# schmatic.net
KiCad netlist of a schematic drawn in EAGLE
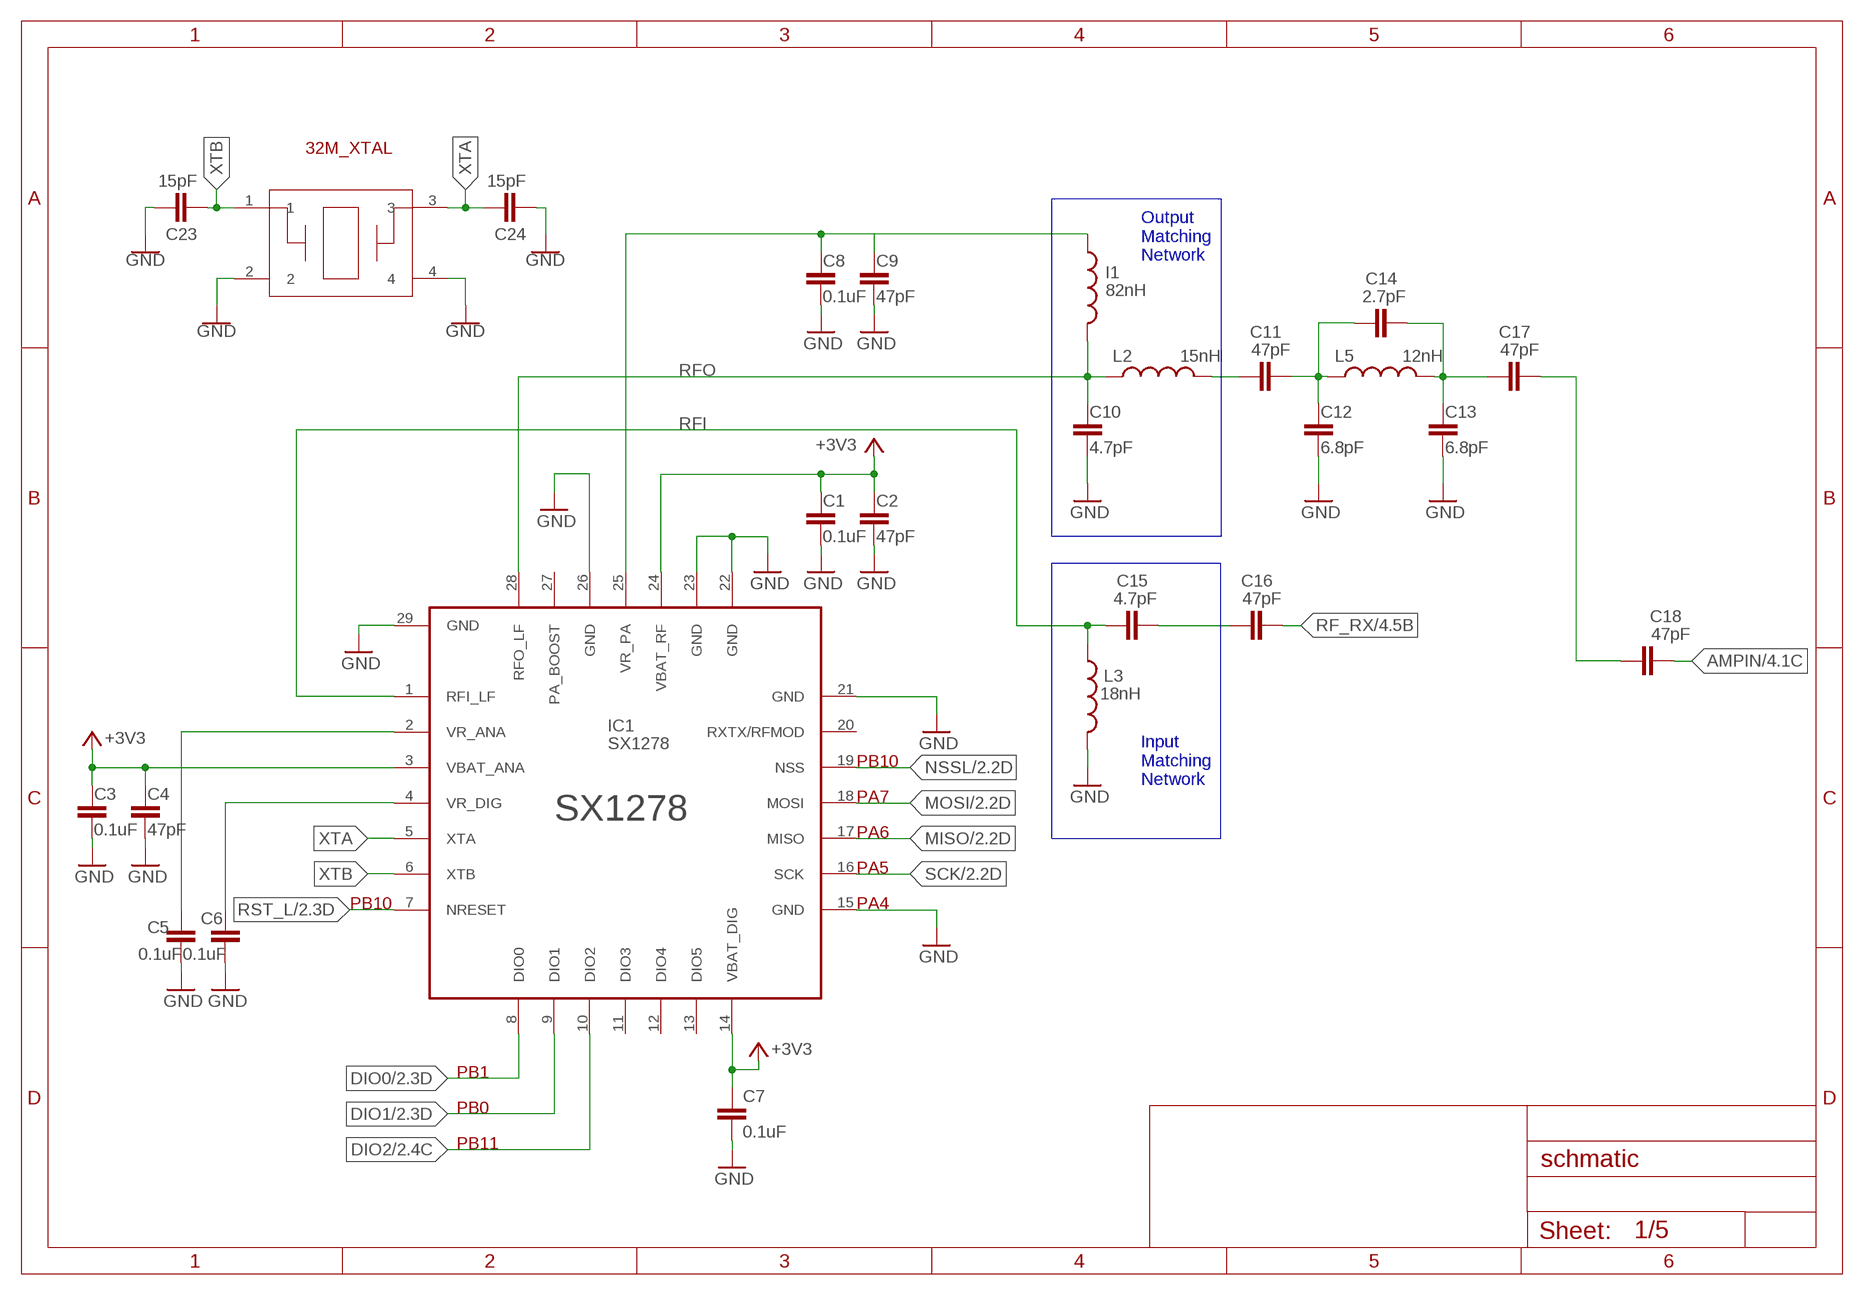
[diagram p0: schematic, sheet 1]
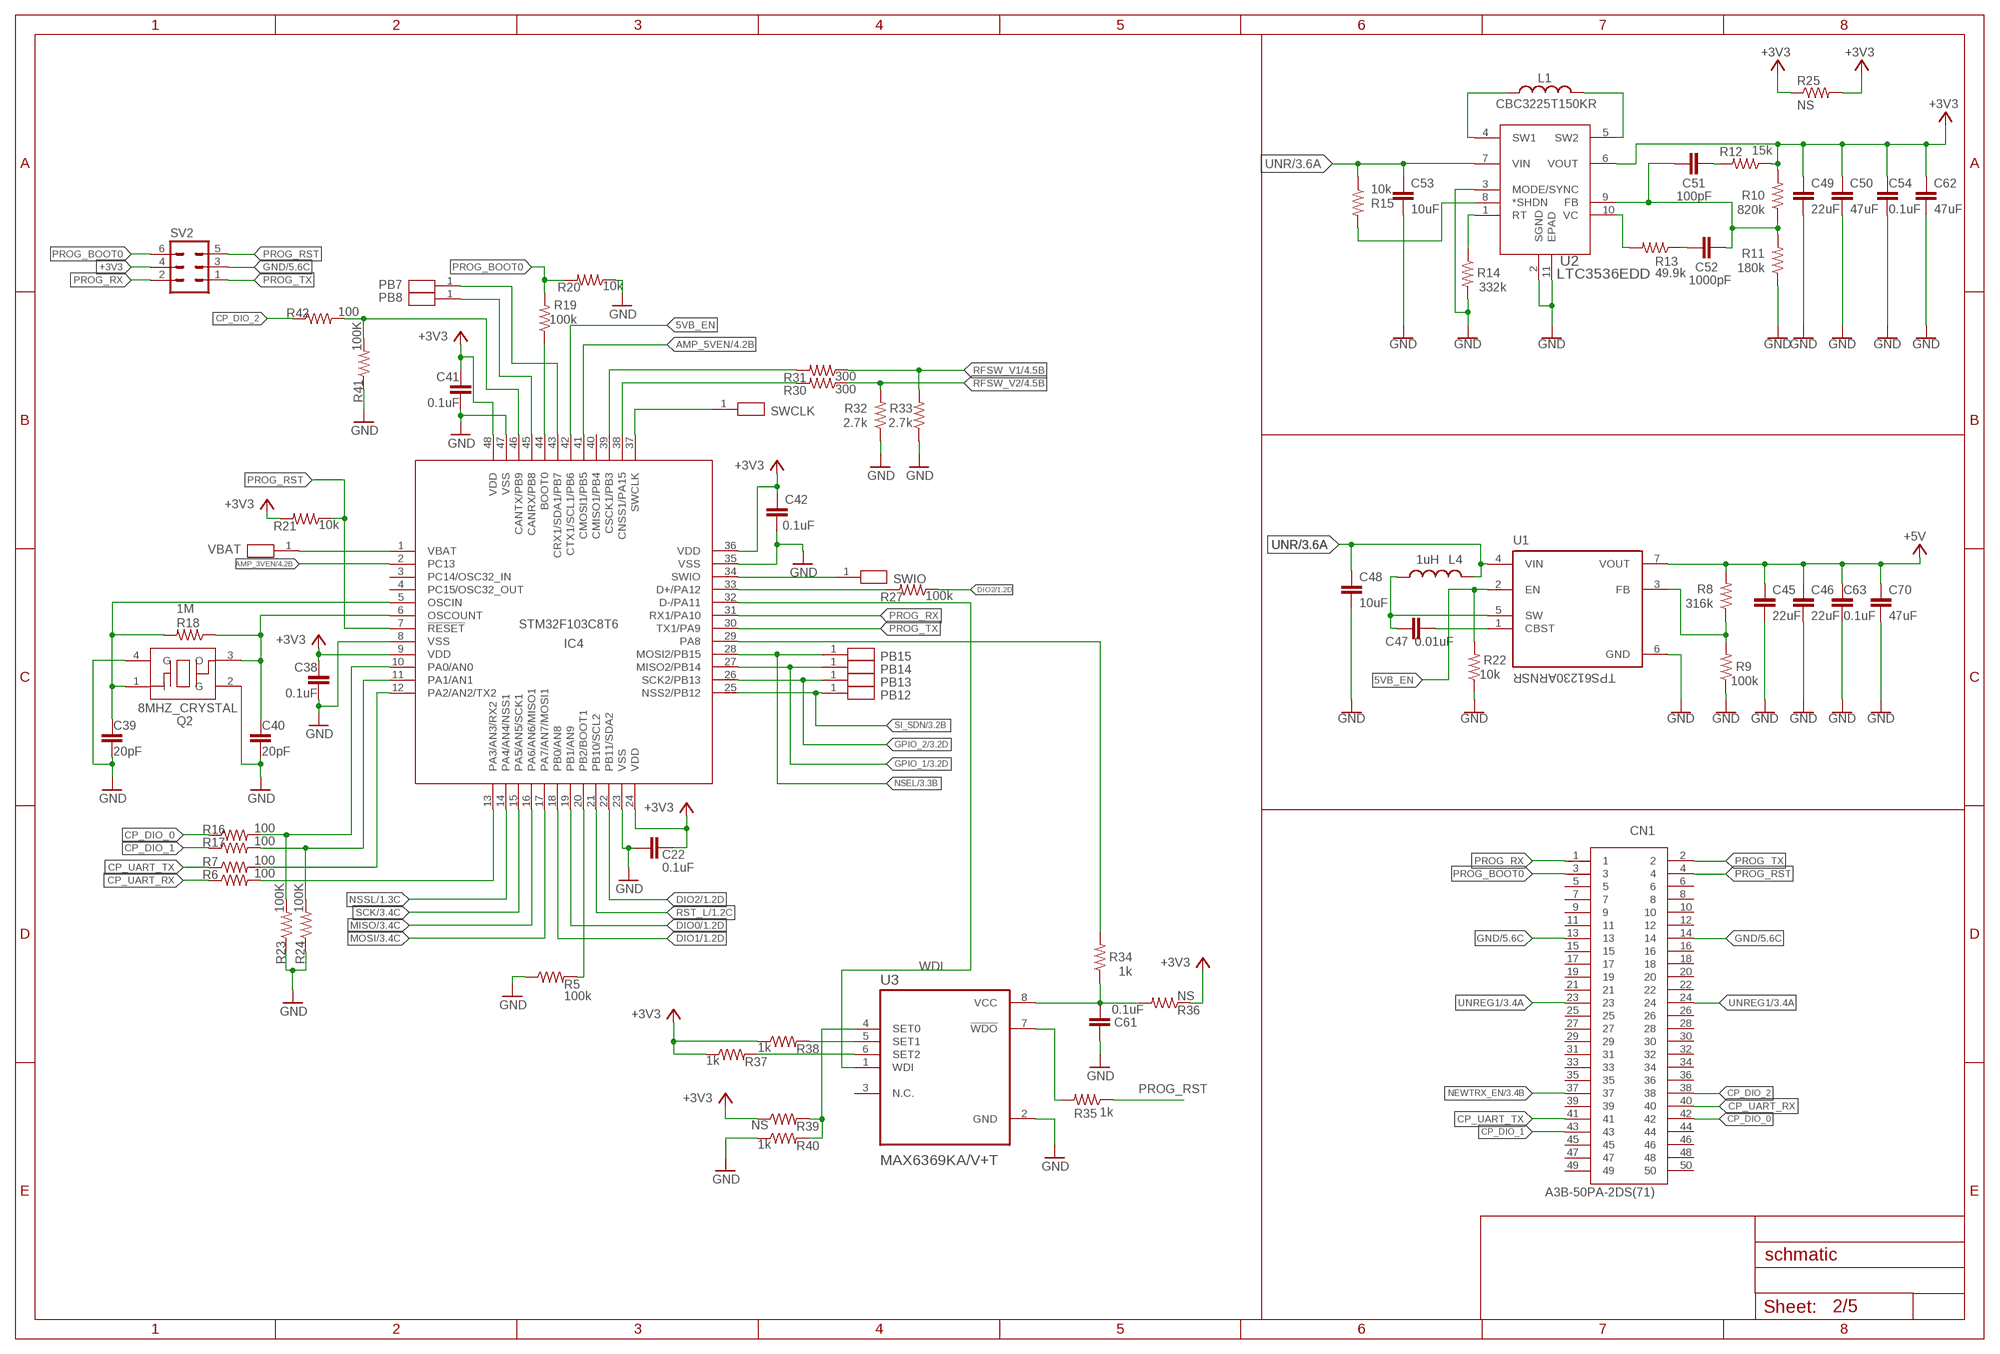
[diagram p1: schematic, sheet 2]
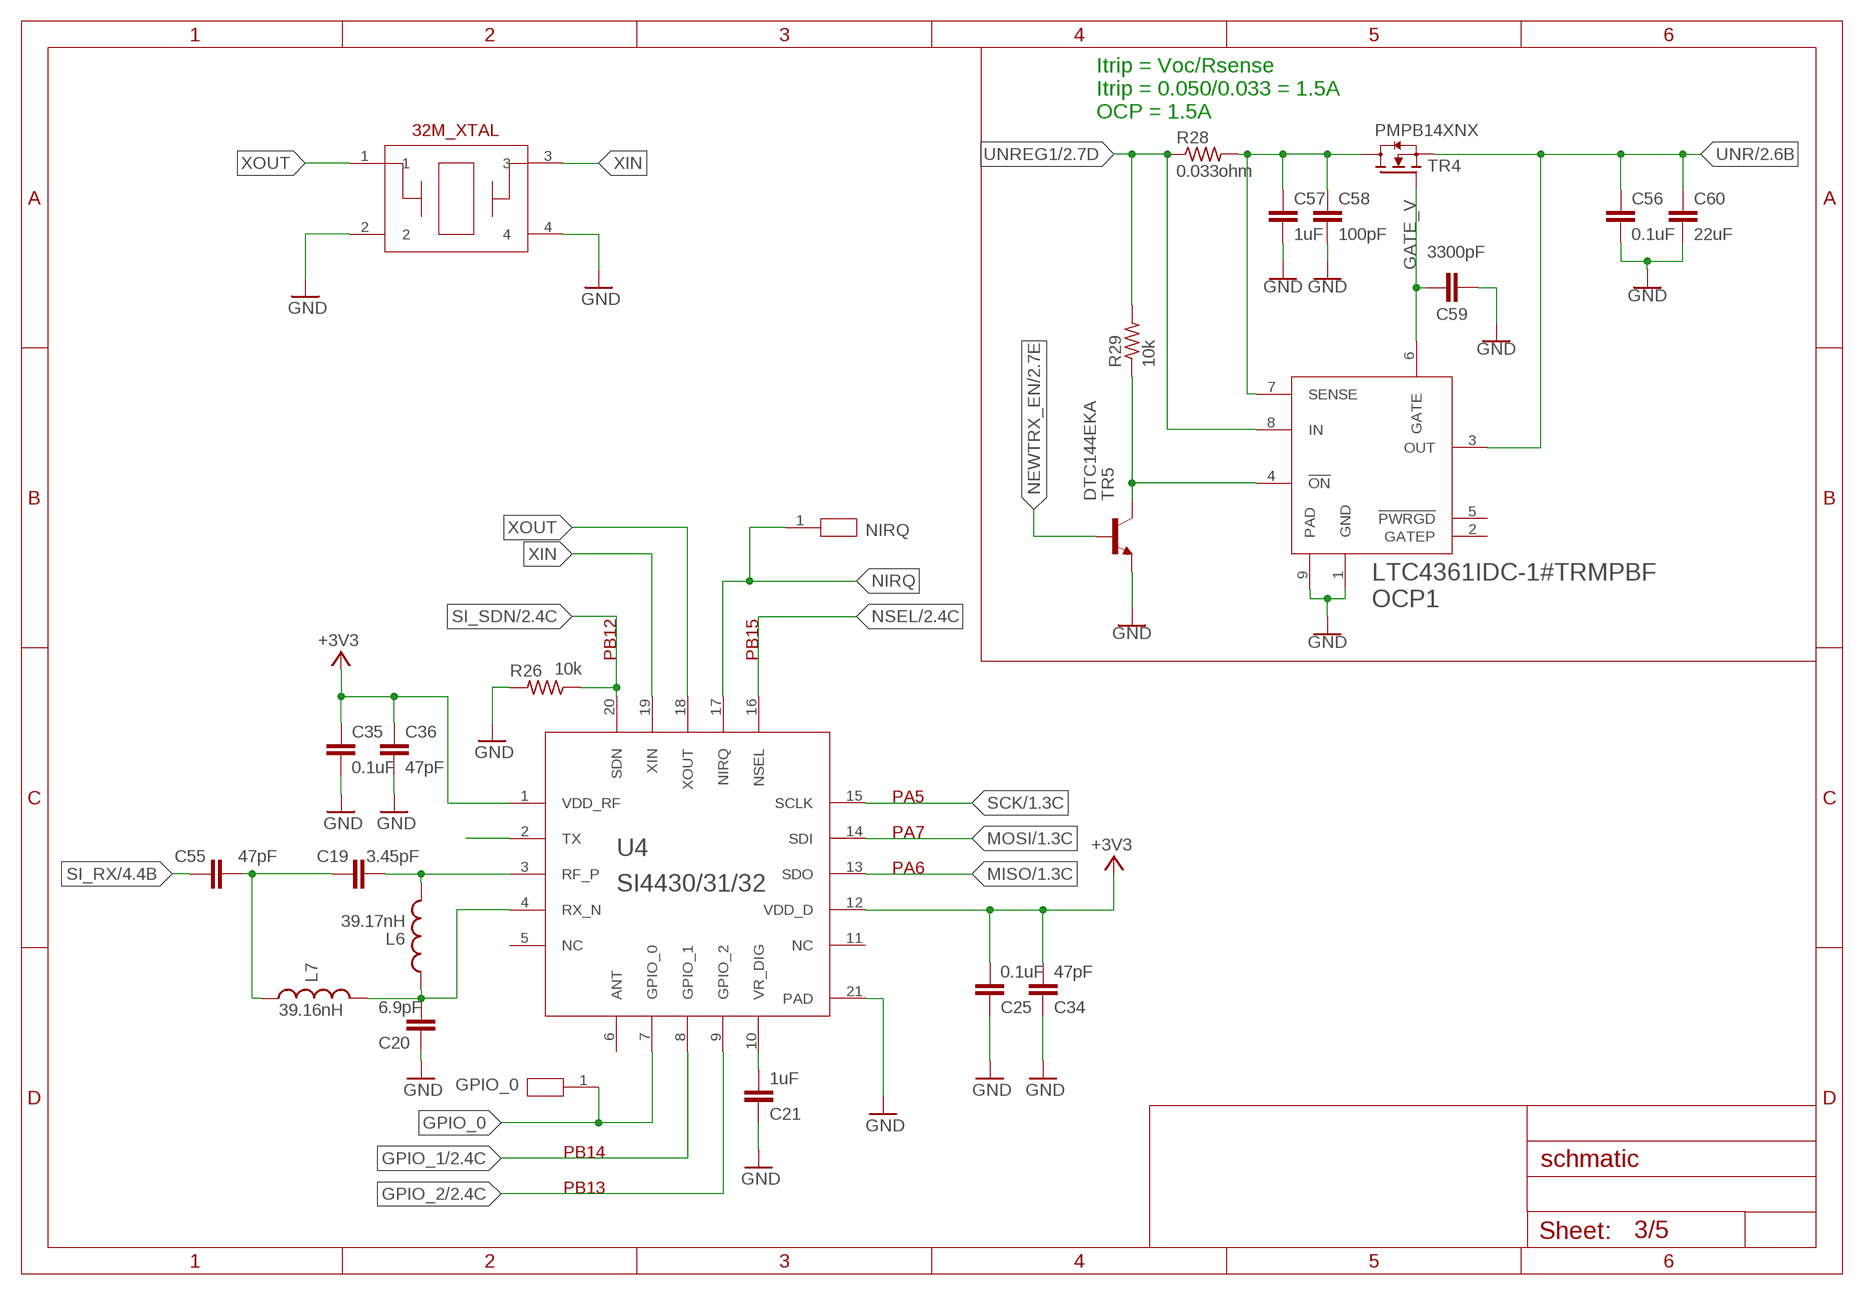
[diagram p2: schematic, sheet 3]
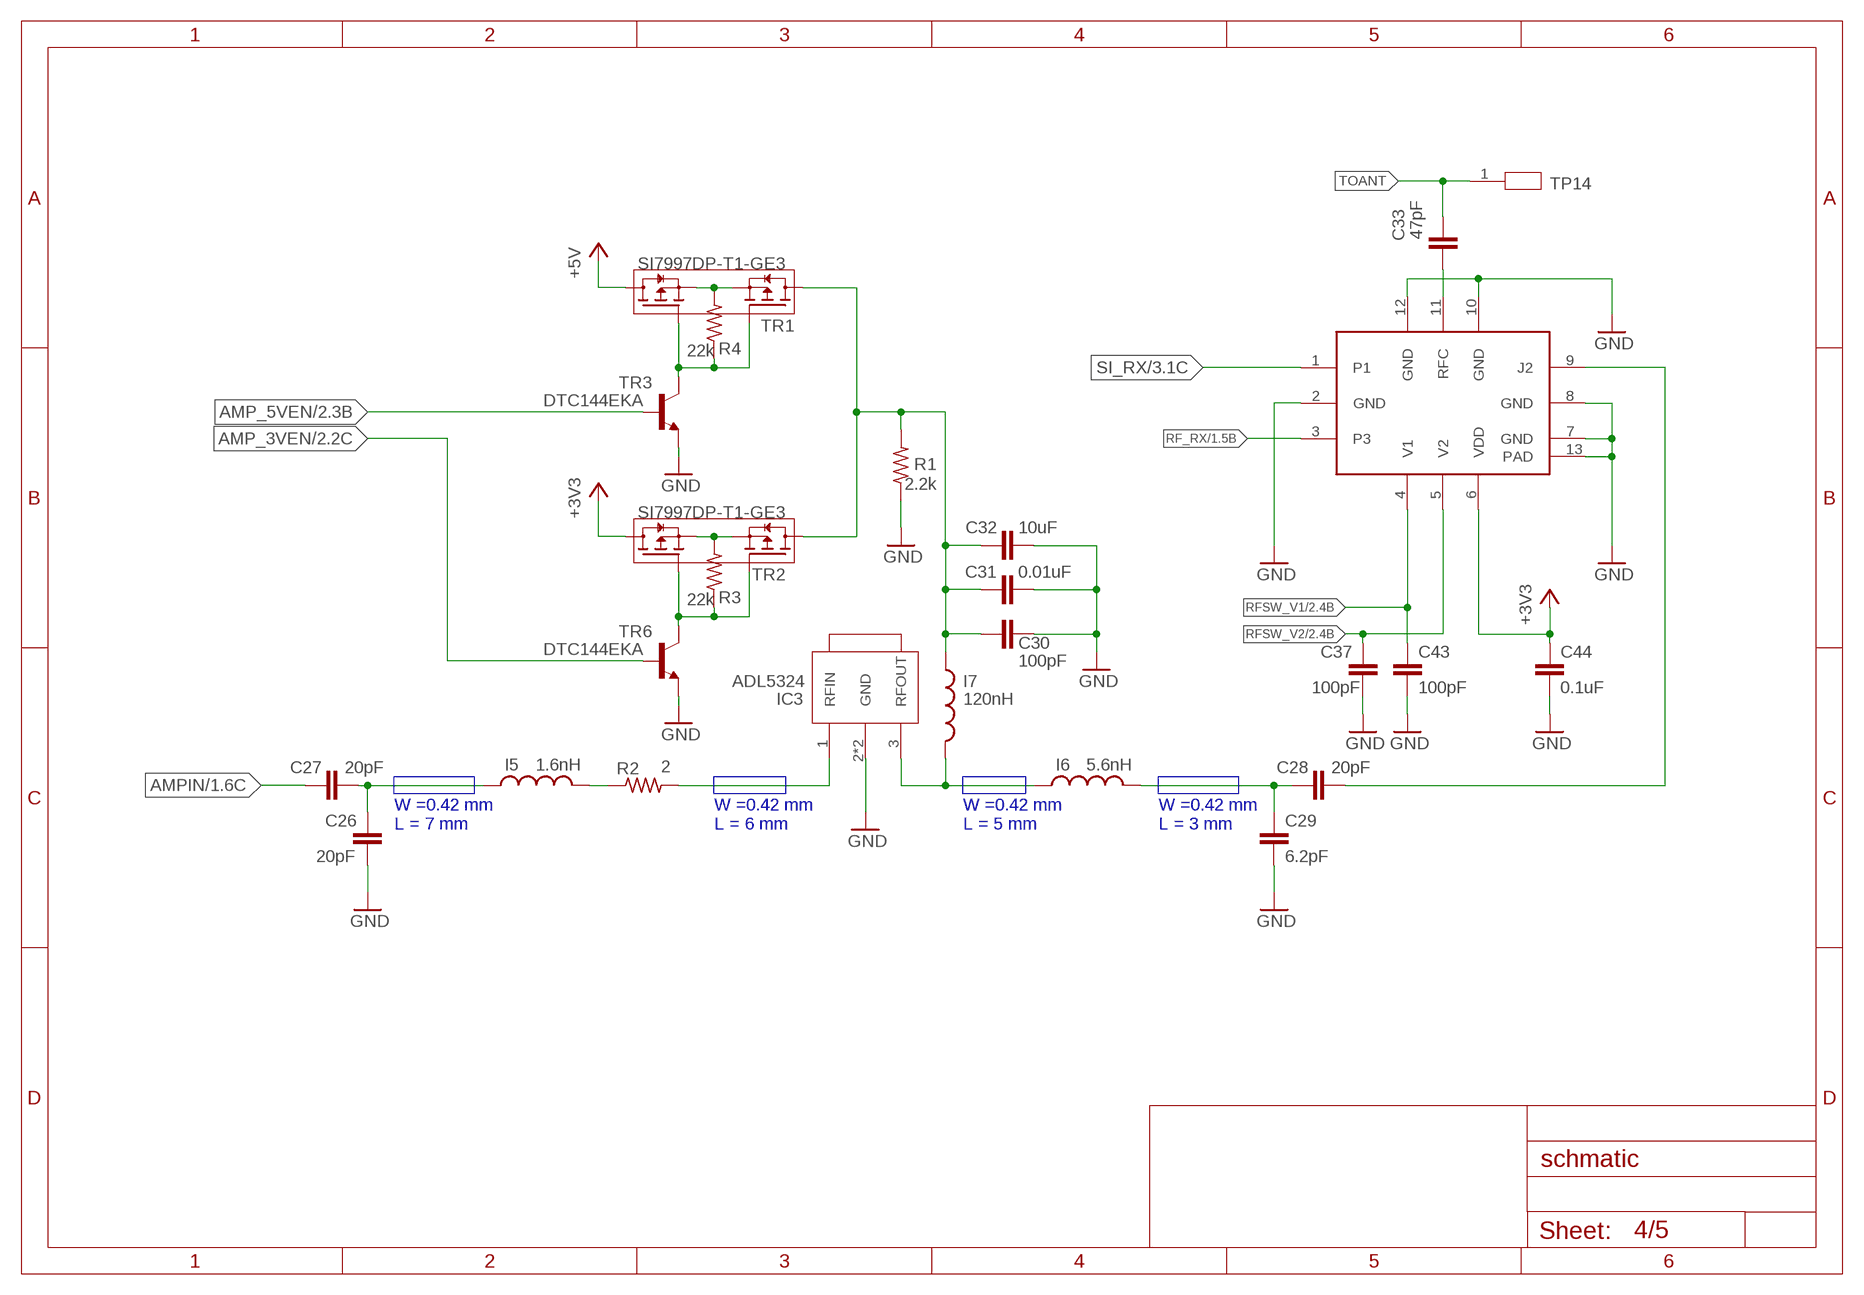
[diagram p3: schematic, sheet 4]
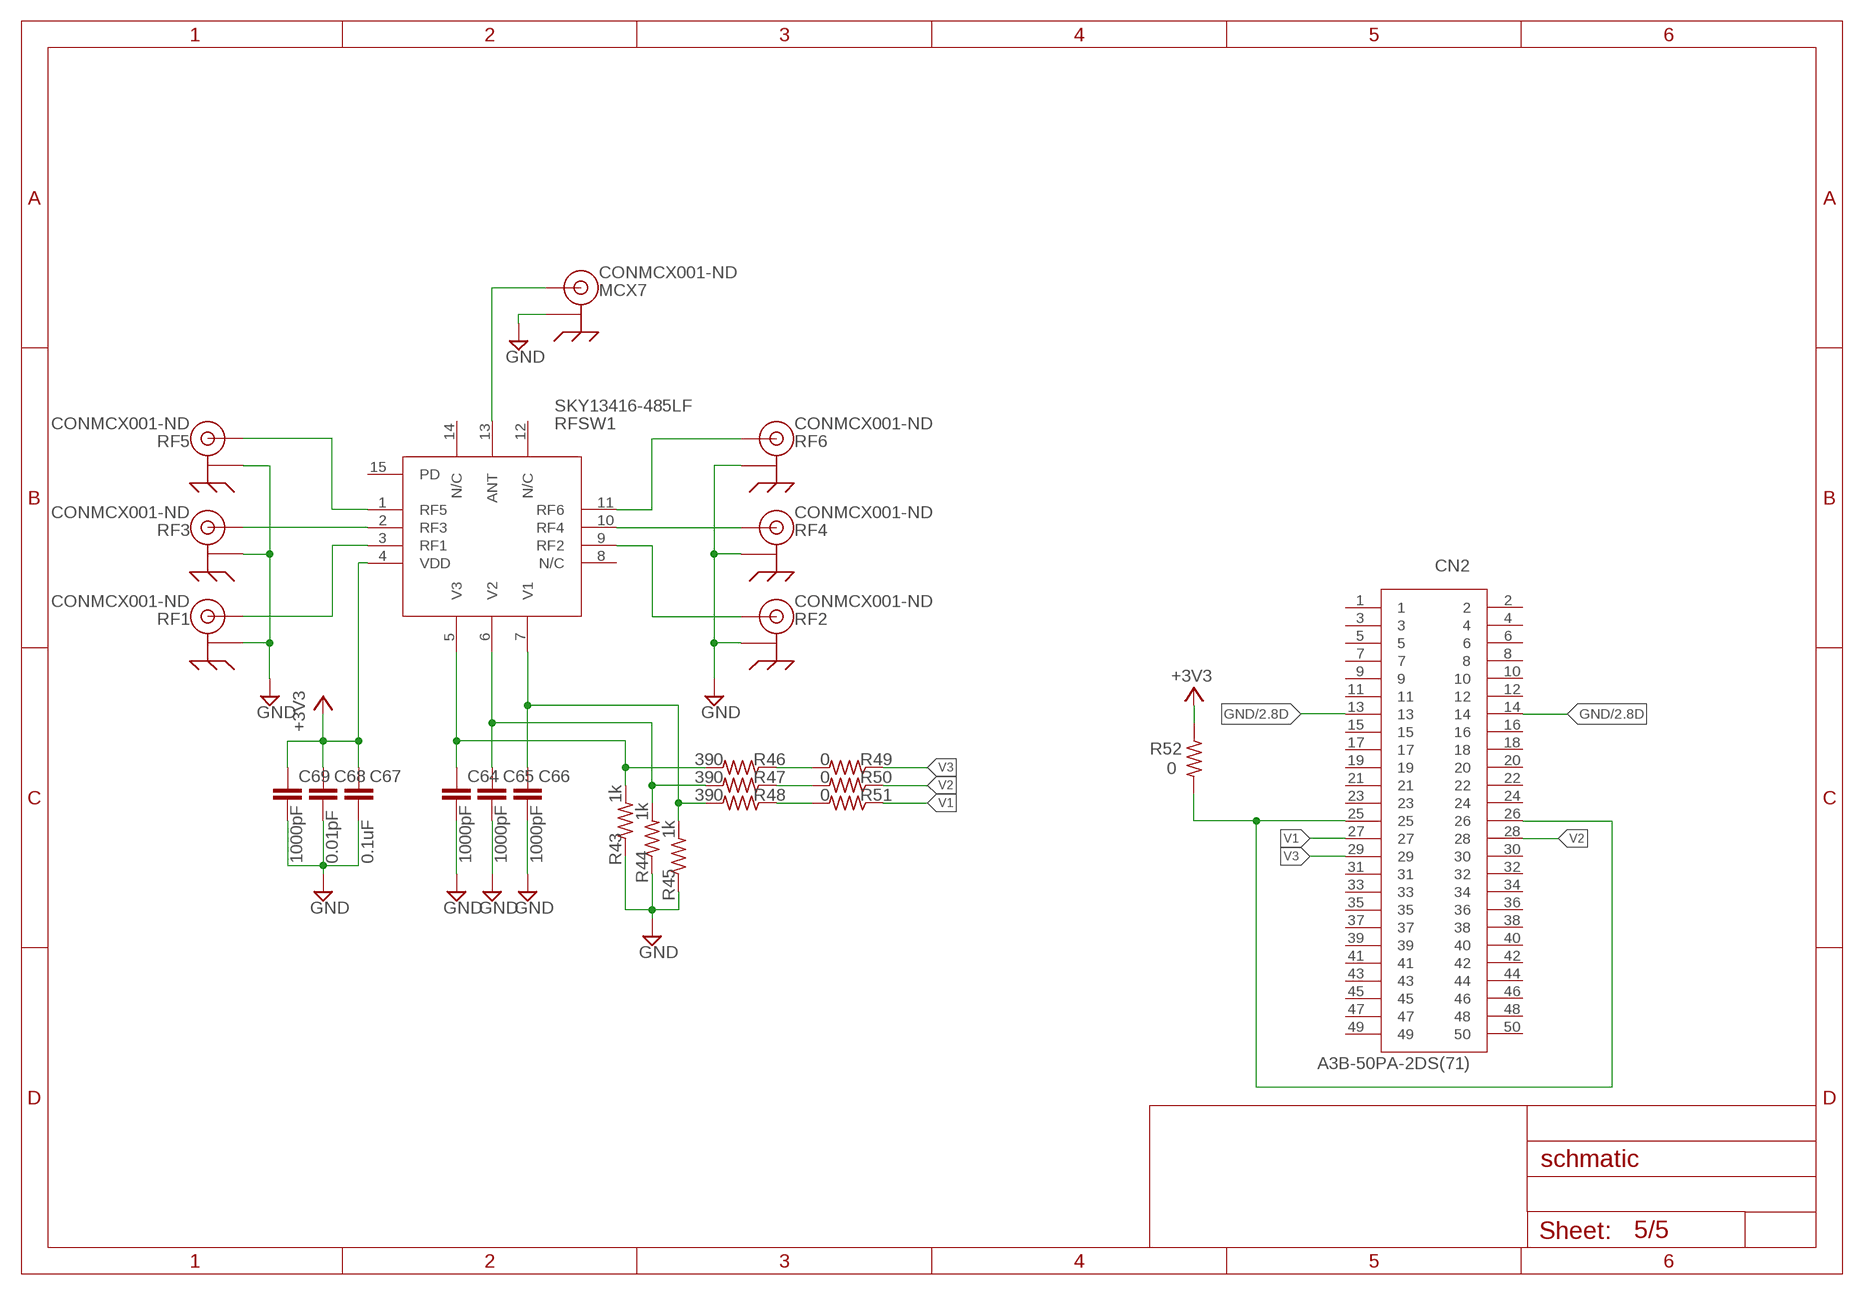
[diagram p4: schematic, sheet 5]

(export (version "E")
  (design (tool "Eeschema 10.0.6"))
  (components
    (comp (ref "C64")
      (value "1000pF")
      (footprint "eagle-import:M(1005)_US(0402)")
      (libsource (lib "eagle-import") (part "CAPACITOR"))
    )
    (comp (ref "C65")
      (value "1000pF")
      (footprint "eagle-import:M(1005)_US(0402)")
      (libsource (lib "eagle-import") (part "CAPACITOR"))
    )
    (comp (ref "C66")
      (value "1000pF")
      (footprint "eagle-import:M(1005)_US(0402)")
      (libsource (lib "eagle-import") (part "CAPACITOR"))
    )
    (comp (ref "C67")
      (value "0.1uF")
      (footprint "eagle-import:M(1005)_US(0402)")
      (libsource (lib "eagle-import") (part "CAPACITOR"))
    )
    (comp (ref "C68")
      (value "0.01pF")
      (footprint "eagle-import:M(1005)_US(0402)")
      (libsource (lib "eagle-import") (part "CAPACITOR"))
    )
    (comp (ref "C69")
      (value "1000pF")
      (footprint "eagle-import:M(1005)_US(0402)")
      (libsource (lib "eagle-import") (part "CAPACITOR"))
    )
    (comp (ref "CN2")
      (value "A3B-50PA-2DS(71)")
      (footprint "eagle-import:A3B-50PA-2DS(71)")
      (libsource (lib "eagle-import") (part "A3B-50PA-2DS(71)"))
    )
    (comp (ref "MCX7")
      (value "CONMCX001-ND")
      (footprint "eagle-import:CONMCX001-ND")
      (libsource (lib "eagle-import") (part "CONMCX001-ND"))
    )
    (comp (ref "R43")
      (value "1k")
      (footprint "eagle-import:M(1608)_US(0603)")
      (libsource (lib "eagle-import") (part "RESISTOR1608"))
    )
    (comp (ref "R44")
      (value "1k")
      (footprint "eagle-import:M(1608)_US(0603)")
      (libsource (lib "eagle-import") (part "RESISTOR1608"))
    )
    (comp (ref "R45")
      (value "1k")
      (footprint "eagle-import:M(1608)_US(0603)")
      (libsource (lib "eagle-import") (part "RESISTOR1608"))
    )
    (comp (ref "R46")
      (value "390")
      (footprint "eagle-import:M(1608)_US(0603)")
      (libsource (lib "eagle-import") (part "RESISTOR1608"))
    )
    (comp (ref "R47")
      (value "390")
      (footprint "eagle-import:M(1608)_US(0603)")
      (libsource (lib "eagle-import") (part "RESISTOR1608"))
    )
    (comp (ref "R48")
      (value "390")
      (footprint "eagle-import:M(1608)_US(0603)")
      (libsource (lib "eagle-import") (part "RESISTOR1608"))
    )
    (comp (ref "R49")
      (value "0")
      (footprint "eagle-import:M(1608)_US(0603)")
      (libsource (lib "eagle-import") (part "RESISTOR1608"))
    )
    (comp (ref "R50")
      (value "0")
      (footprint "eagle-import:M(1608)_US(0603)")
      (libsource (lib "eagle-import") (part "RESISTOR1608"))
    )
    (comp (ref "R51")
      (value "0")
      (footprint "eagle-import:M(1608)_US(0603)")
      (libsource (lib "eagle-import") (part "RESISTOR1608"))
    )
    (comp (ref "R52")
      (value "0")
      (footprint "eagle-import:M(1608)_US(0603)")
      (libsource (lib "eagle-import") (part "RESISTOR1608"))
    )
    (comp (ref "RF1")
      (value "CONMCX001-ND")
      (footprint "eagle-import:CONMCX001-ND")
      (libsource (lib "eagle-import") (part "CONMCX001-ND"))
    )
    (comp (ref "RF2")
      (value "CONMCX001-ND")
      (footprint "eagle-import:CONMCX001-ND")
      (libsource (lib "eagle-import") (part "CONMCX001-ND"))
    )
    (comp (ref "RF3")
      (value "CONMCX001-ND")
      (footprint "eagle-import:CONMCX001-ND")
      (libsource (lib "eagle-import") (part "CONMCX001-ND"))
    )
    (comp (ref "RF4")
      (value "CONMCX001-ND")
      (footprint "eagle-import:CONMCX001-ND")
      (libsource (lib "eagle-import") (part "CONMCX001-ND"))
    )
    (comp (ref "RF5")
      (value "CONMCX001-ND")
      (footprint "eagle-import:CONMCX001-ND")
      (libsource (lib "eagle-import") (part "CONMCX001-ND"))
    )
    (comp (ref "RF6")
      (value "CONMCX001-ND")
      (footprint "eagle-import:CONMCX001-ND")
      (libsource (lib "eagle-import") (part "CONMCX001-ND"))
    )
    (comp (ref "RFSW1")
      (value "SKY13416-485LF")
      (footprint "eagle-import:SKY13416-485LF")
      (libsource (lib "eagle-import") (part "SKY13416-485LF"))
    )
    (comp (ref "C22")
      (value "0.1uF")
      (footprint "eagle-import:M(1005)_US(0402)")
      (libsource (lib "eagle-import") (part "CAPACITOR"))
    )
    (comp (ref "C38")
      (value "0.1uF")
      (footprint "eagle-import:M(1005)_US(0402)")
      (libsource (lib "eagle-import") (part "CAPACITOR"))
    )
    (comp (ref "C39")
      (value "20pF")
      (footprint "eagle-import:M(1005)_US(0402)")
      (libsource (lib "eagle-import") (part "CAPACITOR"))
    )
    (comp (ref "C40")
      (value "20pF")
      (footprint "eagle-import:M(1005)_US(0402)")
      (libsource (lib "eagle-import") (part "CAPACITOR"))
    )
    (comp (ref "C41")
      (value "0.1uF")
      (footprint "eagle-import:M(1005)_US(0402)")
      (libsource (lib "eagle-import") (part "CAPACITOR"))
    )
    (comp (ref "C42")
      (value "0.1uF")
      (footprint "eagle-import:M(1005)_US(0402)")
      (libsource (lib "eagle-import") (part "CAPACITOR"))
    )
    (comp (ref "C45")
      (value "22uF")
      (footprint "eagle-import:M(1608)_US(0603)")
      (libsource (lib "eagle-import") (part "CAPACITOR1608"))
    )
    (comp (ref "C46")
      (value "22uF")
      (footprint "eagle-import:M(1608)_US(0603)")
      (libsource (lib "eagle-import") (part "CAPACITOR1608"))
    )
    (comp (ref "C47")
      (value "0.01uF")
      (footprint "eagle-import:M(1005)_US(0402)")
      (libsource (lib "eagle-import") (part "CAPACITOR"))
    )
    (comp (ref "C48")
      (value "10uF")
      (footprint "eagle-import:M(1608)_US(0603)")
      (libsource (lib "eagle-import") (part "CAPACITOR1608"))
    )
    (comp (ref "C49")
      (value "22uF")
      (footprint "eagle-import:M(1608)_US(0603)")
      (libsource (lib "eagle-import") (part "CAPACITOR1608"))
    )
    (comp (ref "C50")
      (value "47uF")
      (footprint "eagle-import:M(2012)_US(0805)")
      (libsource (lib "eagle-import") (part "CAPACITOR2012"))
    )
    (comp (ref "C51")
      (value "100pF")
      (footprint "eagle-import:M(1005)_US(0402)")
      (libsource (lib "eagle-import") (part "CAPACITOR"))
    )
    (comp (ref "C52")
      (value "1000pF")
      (footprint "eagle-import:M(1005)_US(0402)")
      (libsource (lib "eagle-import") (part "CAPACITOR"))
    )
    (comp (ref "C53")
      (value "10uF")
      (footprint "eagle-import:M(1608)_US(0603)")
      (libsource (lib "eagle-import") (part "CAPACITOR1608"))
    )
    (comp (ref "C54")
      (value "0.1uF")
      (footprint "eagle-import:M(1005)_US(0402)")
      (libsource (lib "eagle-import") (part "CAPACITOR"))
    )
    (comp (ref "C61")
      (value "0.1uF")
      (footprint "eagle-import:M(1005)_US(0402)")
      (libsource (lib "eagle-import") (part "CAPACITOR"))
    )
    (comp (ref "C62")
      (value "47uF")
      (footprint "eagle-import:M(2012)_US(0805)")
      (libsource (lib "eagle-import") (part "CAPACITOR2012"))
    )
    (comp (ref "C63")
      (value "0.1uF")
      (footprint "eagle-import:M(1005)_US(0402)")
      (libsource (lib "eagle-import") (part "CAPACITOR"))
    )
    (comp (ref "C70")
      (value "47uF")
      (footprint "eagle-import:M(2012)_US(0805)")
      (libsource (lib "eagle-import") (part "CAPACITOR2012"))
    )
    (comp (ref "CN1")
      (value "A3B-50PA-2DS(71)")
      (footprint "eagle-import:A3B-50PA-2DS(71)")
      (libsource (lib "eagle-import") (part "A3B-50PA-2DS(71)"))
    )
    (comp (ref "IC4")
      (value "STM32F103C8T6")
      (footprint "eagle-import:STM32F103C8T6")
      (libsource (lib "eagle-import") (part "STM32F103C8T6"))
    )
    (comp (ref "L1")
      (value "CBC3225T150KR")
      (footprint "eagle-import:M(3225)_US(1210)")
      (libsource (lib "eagle-import") (part "INDUCTOR3225"))
    )
    (comp (ref "L4")
      (value "1uH")
      (footprint "eagle-import:AMDLA3020S-1R5MT")
      (libsource (lib "eagle-import") (part "AMDLA3020S-1R5MT"))
    )
    (comp (ref "PB7")
      (value "TEST_POINT")
      (footprint "eagle-import:TEST_POINT_1.5MM")
      (libsource (lib "eagle-import") (part "TEST_POINT"))
    )
    (comp (ref "PB8")
      (value "TEST_POINT")
      (footprint "eagle-import:TEST_POINT_1.5MM")
      (libsource (lib "eagle-import") (part "TEST_POINT"))
    )
    (comp (ref "PB12")
      (value "TEST_POINT")
      (footprint "eagle-import:TEST_POINT_1.5MM")
      (libsource (lib "eagle-import") (part "TEST_POINT"))
    )
    (comp (ref "PB13")
      (value "TEST_POINT")
      (footprint "eagle-import:TEST_POINT_1.5MM")
      (libsource (lib "eagle-import") (part "TEST_POINT"))
    )
    (comp (ref "PB14")
      (value "TEST_POINT")
      (footprint "eagle-import:TEST_POINT_1.5MM")
      (libsource (lib "eagle-import") (part "TEST_POINT"))
    )
    (comp (ref "PB15")
      (value "TEST_POINT")
      (footprint "eagle-import:TEST_POINT_1.5MM")
      (libsource (lib "eagle-import") (part "TEST_POINT"))
    )
    (comp (ref "Q2")
      (value "8MHZ_CRYSTAL")
      (footprint "eagle-import:ECS-80-18-30B-JEM-TR")
      (libsource (lib "eagle-import") (part "8MHZ_CRYSTAL"))
    )
    (comp (ref "R5")
      (value "100k")
      (footprint "eagle-import:M(1005)_US(0402)")
      (libsource (lib "eagle-import") (part "Tharindu_lib_RESISTOR"))
    )
    (comp (ref "R6")
      (value "100")
      (footprint "eagle-import:M(1005)_US(0402)")
      (libsource (lib "eagle-import") (part "Tharindu_lib_RESISTOR"))
    )
    (comp (ref "R7")
      (value "100")
      (footprint "eagle-import:M(1005)_US(0402)")
      (libsource (lib "eagle-import") (part "Tharindu_lib_RESISTOR"))
    )
    (comp (ref "R8")
      (value "316k")
      (footprint "eagle-import:M(1608)_US(0603)")
      (libsource (lib "eagle-import") (part "RESISTOR1608"))
    )
    (comp (ref "R9")
      (value "100k")
      (footprint "eagle-import:M(1608)_US(0603)")
      (libsource (lib "eagle-import") (part "RESISTOR1608"))
    )
    (comp (ref "R10")
      (value "820k")
      (footprint "eagle-import:M(1608)_US(0603)")
      (libsource (lib "eagle-import") (part "RESISTOR1608"))
    )
    (comp (ref "R11")
      (value "180k")
      (footprint "eagle-import:M(1608)_US(0603)")
      (libsource (lib "eagle-import") (part "RESISTOR1608"))
    )
    (comp (ref "R12")
      (value "15k")
      (footprint "eagle-import:M(1608)_US(0603)")
      (libsource (lib "eagle-import") (part "RESISTOR1608"))
    )
    (comp (ref "R13")
      (value "49.9k")
      (footprint "eagle-import:M(1608)_US(0603)")
      (libsource (lib "eagle-import") (part "RESISTOR1608"))
    )
    (comp (ref "R14")
      (value "332k")
      (footprint "eagle-import:M(1608)_US(0603)")
      (libsource (lib "eagle-import") (part "RESISTOR1608"))
    )
    (comp (ref "R15")
      (value "10k")
      (footprint "eagle-import:M(1005)_US(0402)")
      (libsource (lib "eagle-import") (part "Tharindu_lib_RESISTOR"))
    )
    (comp (ref "R16")
      (value "100")
      (footprint "eagle-import:M(1005)_US(0402)")
      (libsource (lib "eagle-import") (part "Tharindu_lib_RESISTOR"))
    )
    (comp (ref "R17")
      (value "100")
      (footprint "eagle-import:M(1005)_US(0402)")
      (libsource (lib "eagle-import") (part "Tharindu_lib_RESISTOR"))
    )
    (comp (ref "R18")
      (value "1M")
      (footprint "eagle-import:M(1608)_US(0603)")
      (libsource (lib "eagle-import") (part "RESISTOR1608"))
    )
    (comp (ref "R19")
      (value "100k")
      (footprint "eagle-import:M(1005)_US(0402)")
      (libsource (lib "eagle-import") (part "Tharindu_lib_RESISTOR"))
    )
    (comp (ref "R20")
      (value "10k")
      (footprint "eagle-import:M(1005)_US(0402)")
      (libsource (lib "eagle-import") (part "Tharindu_lib_RESISTOR"))
    )
    (comp (ref "R21")
      (value "10k")
      (footprint "eagle-import:M(1005)_US(0402)")
      (libsource (lib "eagle-import") (part "Tharindu_lib_RESISTOR"))
    )
    (comp (ref "R22")
      (value "10k")
      (footprint "eagle-import:M(1005)_US(0402)")
      (libsource (lib "eagle-import") (part "Tharindu_lib_RESISTOR"))
    )
    (comp (ref "R23")
      (value "100K")
      (footprint "eagle-import:M(1005)_US(0402)")
      (libsource (lib "eagle-import") (part "Tharindu_lib_RESISTOR"))
    )
    (comp (ref "R24")
      (value "100K")
      (footprint "eagle-import:M(1005)_US(0402)")
      (libsource (lib "eagle-import") (part "Tharindu_lib_RESISTOR"))
    )
    (comp (ref "R25")
      (value "NS")
      (footprint "eagle-import:M(2012)_US(0805)")
      (libsource (lib "eagle-import") (part "RESISTOR2012"))
    )
    (comp (ref "R27")
      (value "100k")
      (footprint "eagle-import:M(1005)_US(0402)")
      (libsource (lib "eagle-import") (part "Tharindu_lib_RESISTOR"))
    )
    (comp (ref "R30")
      (value "300")
      (footprint "eagle-import:M(1608)_US(0603)")
      (libsource (lib "eagle-import") (part "RESISTOR1608"))
    )
    (comp (ref "R31")
      (value "300")
      (footprint "eagle-import:M(1608)_US(0603)")
      (libsource (lib "eagle-import") (part "RESISTOR1608"))
    )
    (comp (ref "R32")
      (value "2.7k")
      (footprint "eagle-import:M(1608)_US(0603)")
      (libsource (lib "eagle-import") (part "RESISTOR1608"))
    )
    (comp (ref "R33")
      (value "2.7k")
      (footprint "eagle-import:M(1608)_US(0603)")
      (libsource (lib "eagle-import") (part "RESISTOR1608"))
    )
    (comp (ref "R34")
      (value "1k")
      (footprint "eagle-import:M(1608)_US(0603)")
      (libsource (lib "eagle-import") (part "RESISTOR1608"))
    )
    (comp (ref "R35")
      (value "1k")
      (footprint "eagle-import:M(1608)_US(0603)")
      (libsource (lib "eagle-import") (part "RESISTOR1608"))
    )
    (comp (ref "R36")
      (value "NS")
      (footprint "eagle-import:M(1608)_US(0603)")
      (libsource (lib "eagle-import") (part "RESISTOR1608"))
    )
    (comp (ref "R37")
      (value "1k")
      (footprint "eagle-import:M(1005)_US(0402)")
      (libsource (lib "eagle-import") (part "Tharindu_lib_RESISTOR"))
    )
    (comp (ref "R38")
      (value "1k")
      (footprint "eagle-import:M(1005)_US(0402)")
      (libsource (lib "eagle-import") (part "Tharindu_lib_RESISTOR"))
    )
    (comp (ref "R39")
      (value "NS")
      (footprint "eagle-import:M(1005)_US(0402)")
      (libsource (lib "eagle-import") (part "Tharindu_lib_RESISTOR"))
    )
    (comp (ref "R40")
      (value "1k")
      (footprint "eagle-import:M(1005)_US(0402)")
      (libsource (lib "eagle-import") (part "Tharindu_lib_RESISTOR"))
    )
    (comp (ref "R41")
      (value "100K")
      (footprint "eagle-import:M(1005)_US(0402)")
      (libsource (lib "eagle-import") (part "Tharindu_lib_RESISTOR"))
    )
    (comp (ref "R42")
      (value "100")
      (footprint "eagle-import:M(1005)_US(0402)")
      (libsource (lib "eagle-import") (part "Tharindu_lib_RESISTOR"))
    )
    (comp (ref "SV2")
      (value "MA03-2")
      (footprint "eagle-import:MA03-2")
      (libsource (lib "eagle-import") (part "MA03-2"))
    )
    (comp (ref "SWCLK")
      (value "TEST_POINT")
      (footprint "eagle-import:TEST_POINT_1.5MM")
      (libsource (lib "eagle-import") (part "TEST_POINT"))
    )
    (comp (ref "SWIO")
      (value "TEST_POINT")
      (footprint "eagle-import:TEST_POINT_1.5MM")
      (libsource (lib "eagle-import") (part "TEST_POINT"))
    )
    (comp (ref "U1")
      (value "TPS61230ARNSR")
      (footprint "eagle-import:IC_TPS61230ARNSR")
      (fields (field (name "MF") "Texas Instruments"))
      (libsource (lib "eagle-import") (part "TPS61230ARNSR"))
    )
    (comp (ref "U2")
      (value "LTC3536EDD")
      (footprint "eagle-import:DFN-10_DD")
      (fields (field (name "MF") "Analog Devices") (field (name "MP") "LTC3536EDD#TRPBF"))
      (libsource (lib "eagle-import") (part "LTC3536EDD#TRPBF"))
    )
    (comp (ref "U3")
      (value "MAX6369KA/V+T")
      (footprint "eagle-import:SOT65P280X145-8N")
      (fields (field (name "MF") "Analog Devices"))
      (libsource (lib "eagle-import") (part "MAX6369KA/V+T"))
    )
    (comp (ref "VBAT")
      (value "TEST_POINT")
      (footprint "eagle-import:TEST_POINT_1.5MM")
      (libsource (lib "eagle-import") (part "TEST_POINT"))
    )
    (comp (ref "C19")
      (value "3.45pF")
      (footprint "eagle-import:M(1005)_US(0402)")
      (libsource (lib "eagle-import") (part "CAPACITOR"))
    )
    (comp (ref "C20")
      (value "6.9pF")
      (footprint "eagle-import:M(1005)_US(0402)")
      (libsource (lib "eagle-import") (part "CAPACITOR"))
    )
    (comp (ref "C21")
      (value "1uF")
      (footprint "eagle-import:M(1005)_US(0402)")
      (libsource (lib "eagle-import") (part "CAPACITOR"))
    )
    (comp (ref "C25")
      (value "0.1uF")
      (footprint "eagle-import:M(1005)_US(0402)")
      (libsource (lib "eagle-import") (part "CAPACITOR"))
    )
    (comp (ref "C34")
      (value "47pF")
      (footprint "eagle-import:M(1005)_US(0402)")
      (libsource (lib "eagle-import") (part "CAPACITOR"))
    )
    (comp (ref "C35")
      (value "0.1uF")
      (footprint "eagle-import:M(1608)_US(0603)")
      (libsource (lib "eagle-import") (part "CAPACITOR1608"))
    )
    (comp (ref "C36")
      (value "47pF")
      (footprint "eagle-import:M(1608)_US(0603)")
      (libsource (lib "eagle-import") (part "CAPACITOR1608"))
    )
    (comp (ref "C55")
      (value "47pF")
      (footprint "eagle-import:M(1005)_US(0402)")
      (libsource (lib "eagle-import") (part "CAPACITOR"))
    )
    (comp (ref "C56")
      (value "0.1uF")
      (footprint "eagle-import:CAP_(M1005)_0402")
      (libsource (lib "eagle-import") (part "CAP_(M1005)_0402"))
    )
    (comp (ref "C57")
      (value "1uF")
      (footprint "eagle-import:CAP_(M1005)_0402")
      (libsource (lib "eagle-import") (part "CAP_(M1005)_0402"))
    )
    (comp (ref "C58")
      (value "100pF")
      (footprint "eagle-import:CAP_(M1005)_0402")
      (libsource (lib "eagle-import") (part "CAP_(M1005)_0402"))
    )
    (comp (ref "C59")
      (value "3300pF")
      (footprint "eagle-import:CAP_(M1005)_0402")
      (libsource (lib "eagle-import") (part "CAP_(M1005)_0402"))
    )
    (comp (ref "C60")
      (value "22uF")
      (footprint "eagle-import:M(1608)_US(0603)")
      (libsource (lib "eagle-import") (part "CAPACITOR1608"))
    )
    (comp (ref "GPIO_0")
      (value "TEST_POINT")
      (footprint "eagle-import:TEST_POINT_1.5MM")
      (libsource (lib "eagle-import") (part "TEST_POINT"))
    )
    (comp (ref "L6")
      (value "39.17nH")
      (footprint "eagle-import:M(1005)_US(0402)")
      (libsource (lib "eagle-import") (part "INDUCTOR"))
    )
    (comp (ref "L7")
      (value "39.16nH")
      (footprint "eagle-import:M(1005)_US(0402)")
      (libsource (lib "eagle-import") (part "INDUCTOR"))
    )
    (comp (ref "NIRQ")
      (value "TEST_POINT")
      (footprint "eagle-import:TEST_POINT_1.5MM")
      (libsource (lib "eagle-import") (part "TEST_POINT"))
    )
    (comp (ref "OCP1")
      (value "LTC4361IDC-1#TRMPBF")
      (footprint "eagle-import:LTC4361IDC-1#TRMPBF")
      (libsource (lib "eagle-import") (part "LTC4361IDC-1#TRMPBF"))
    )
    (comp (ref "Q3")
      (value "NX2520SA-30MHZ")
      (footprint "eagle-import:NX2520SA")
      (libsource (lib "eagle-import") (part "NX2520SA-32MHZ"))
    )
    (comp (ref "R26")
      (value "10k")
      (footprint "eagle-import:M(1608)_US(0603)")
      (libsource (lib "eagle-import") (part "RESISTOR1608"))
    )
    (comp (ref "R28")
      (value "0.033ohm")
      (footprint "eagle-import:R0805")
      (libsource (lib "eagle-import") (part "R-US_R0805"))
    )
    (comp (ref "R29")
      (value "10k")
      (footprint "eagle-import:RES_(M1005)_0402")
      (libsource (lib "eagle-import") (part "RESISTOR"))
    )
    (comp (ref "TR4")
      (value "PMPB14XNX")
      (footprint "eagle-import:PMPB14XN")
      (libsource (lib "eagle-import") (part "PMPB14XNX"))
    )
    (comp (ref "TR5")
      (value "DTC144EKA")
      (footprint "eagle-import:SOT346-R")
      (libsource (lib "eagle-import") (part "DTC144EKA"))
    )
    (comp (ref "U4")
      (value "SI4430/31/32")
      (footprint "eagle-import:SI4430_31_32")
      (libsource (lib "eagle-import") (part "SI4430/31/32"))
    )
    (comp (ref "C26")
      (value "20pF")
      (footprint "eagle-import:M(1005)_US(0402)")
      (libsource (lib "eagle-import") (part "CAPACITOR"))
    )
    (comp (ref "C27")
      (value "20pF")
      (footprint "eagle-import:M(1005)_US(0402)")
      (libsource (lib "eagle-import") (part "CAPACITOR"))
    )
    (comp (ref "C28")
      (value "20pF")
      (footprint "eagle-import:M(1005)_US(0402)")
      (libsource (lib "eagle-import") (part "CAPACITOR"))
    )
    (comp (ref "C29")
      (value "6.2pF")
      (footprint "eagle-import:M(1005)_US(0402)")
      (libsource (lib "eagle-import") (part "CAPACITOR"))
    )
    (comp (ref "C30")
      (value "100pF")
      (footprint "eagle-import:M(1005)_US(0402)")
      (libsource (lib "eagle-import") (part "CAPACITOR"))
    )
    (comp (ref "C31")
      (value "0.01uF")
      (footprint "eagle-import:M(1005)_US(0402)")
      (libsource (lib "eagle-import") (part "CAPACITOR"))
    )
    (comp (ref "C32")
      (value "10uF")
      (footprint "eagle-import:M(1608)_US(0603)")
      (libsource (lib "eagle-import") (part "CAPACITOR1608"))
    )
    (comp (ref "C33")
      (value "47pF")
      (footprint "eagle-import:M(1005)_US(0402)")
      (libsource (lib "eagle-import") (part "CAPACITOR"))
    )
    (comp (ref "C37")
      (value "100pF")
      (footprint "eagle-import:M(1005)_US(0402)")
      (libsource (lib "eagle-import") (part "CAPACITOR"))
    )
    (comp (ref "C43")
      (value "100pF")
      (footprint "eagle-import:M(1005)_US(0402)")
      (libsource (lib "eagle-import") (part "CAPACITOR"))
    )
    (comp (ref "C44")
      (value "0.1uF")
      (footprint "eagle-import:M(1005)_US(0402)")
      (libsource (lib "eagle-import") (part "CAPACITOR"))
    )
    (comp (ref "I5")
      (value "1.6nH")
      (footprint "eagle-import:M(1005)_US(0402)")
      (libsource (lib "eagle-import") (part "INDUCTOR"))
    )
    (comp (ref "I6")
      (value "5.6nH")
      (footprint "eagle-import:M(1005)_US(0402)")
      (libsource (lib "eagle-import") (part "INDUCTOR"))
    )
    (comp (ref "I7")
      (value "120nH")
      (footprint "eagle-import:M(2012)_US(0805)")
      (libsource (lib "eagle-import") (part "INDUCTOR2012"))
    )
    (comp (ref "IC3")
      (value "ADL5324")
      (footprint "eagle-import:ADL5324")
      (libsource (lib "eagle-import") (part "ADL5324"))
    )
    (comp (ref "R1")
      (value "2.2k")
      (footprint "eagle-import:M(1608)_US(0603)")
      (libsource (lib "eagle-import") (part "RESISTOR1608"))
    )
    (comp (ref "R2")
      (value "2")
      (footprint "eagle-import:M(1608)_US(0603)")
      (libsource (lib "eagle-import") (part "RESISTOR1608"))
    )
    (comp (ref "R3")
      (value "22k")
      (footprint "eagle-import:M(1608)_US(0603)")
      (libsource (lib "eagle-import") (part "RESISTOR1608"))
    )
    (comp (ref "R4")
      (value "22k")
      (footprint "eagle-import:M(1608)_US(0603)")
      (libsource (lib "eagle-import") (part "RESISTOR1608"))
    )
    (comp (ref "SW1")
      (value "SKY13373-460LF")
      (footprint "eagle-import:SKY13373-460LF")
      (libsource (lib "eagle-import") (part "SKY13373-460LF"))
    )
    (comp (ref "TP14")
      (value "TEST_POINT")
      (footprint "eagle-import:TEST_POINT_1.5MM")
      (libsource (lib "eagle-import") (part "TEST_POINT"))
    )
    (comp (ref "TR1")
      (value "SI7997DP-T1-GE3")
      (footprint "eagle-import:SI7997DP-T1-GE3")
      (libsource (lib "eagle-import") (part "SI7997DP-T1-GE3"))
    )
    (comp (ref "TR2")
      (value "SI7997DP-T1-GE3")
      (footprint "eagle-import:SI7997DP-T1-GE3")
      (libsource (lib "eagle-import") (part "SI7997DP-T1-GE3"))
    )
    (comp (ref "TR3")
      (value "DTC144EKA")
      (footprint "eagle-import:SOT346-R")
      (libsource (lib "eagle-import") (part "DTC144EKA"))
    )
    (comp (ref "TR6")
      (value "DTC144EKA")
      (footprint "eagle-import:SOT346-R")
      (libsource (lib "eagle-import") (part "DTC144EKA"))
    )
    (comp (ref "C1")
      (value "0.1uF")
      (footprint "eagle-import:M(1005)_US(0402)")
      (libsource (lib "eagle-import") (part "CAPACITOR"))
    )
    (comp (ref "C2")
      (value "47pF")
      (footprint "eagle-import:M(1005)_US(0402)")
      (libsource (lib "eagle-import") (part "CAPACITOR"))
    )
    (comp (ref "C3")
      (value "0.1uF")
      (footprint "eagle-import:M(1005)_US(0402)")
      (libsource (lib "eagle-import") (part "CAPACITOR"))
    )
    (comp (ref "C4")
      (value "47pF")
      (footprint "eagle-import:M(1005)_US(0402)")
      (libsource (lib "eagle-import") (part "CAPACITOR"))
    )
    (comp (ref "C5")
      (value "0.1uF")
      (footprint "eagle-import:M(1005)_US(0402)")
      (libsource (lib "eagle-import") (part "CAPACITOR"))
    )
    (comp (ref "C6")
      (value "0.1uF")
      (footprint "eagle-import:M(1005)_US(0402)")
      (libsource (lib "eagle-import") (part "CAPACITOR"))
    )
    (comp (ref "C7")
      (value "0.1uF")
      (footprint "eagle-import:M(1005)_US(0402)")
      (libsource (lib "eagle-import") (part "CAPACITOR"))
    )
    (comp (ref "C8")
      (value "0.1uF")
      (footprint "eagle-import:M(1005)_US(0402)")
      (libsource (lib "eagle-import") (part "CAPACITOR"))
    )
    (comp (ref "C9")
      (value "47pF")
      (footprint "eagle-import:M(1005)_US(0402)")
      (libsource (lib "eagle-import") (part "CAPACITOR"))
    )
    (comp (ref "C10")
      (value "4.7pF")
      (footprint "eagle-import:M(1005)_US(0402)")
      (libsource (lib "eagle-import") (part "CAPACITOR"))
    )
    (comp (ref "C11")
      (value "47pF")
      (footprint "eagle-import:M(1005)_US(0402)")
      (libsource (lib "eagle-import") (part "CAPACITOR"))
    )
    (comp (ref "C12")
      (value "6.8pF")
      (footprint "eagle-import:M(1005)_US(0402)")
      (libsource (lib "eagle-import") (part "CAPACITOR"))
    )
    (comp (ref "C13")
      (value "6.8pF")
      (footprint "eagle-import:M(1005)_US(0402)")
      (libsource (lib "eagle-import") (part "CAPACITOR"))
    )
    (comp (ref "C14")
      (value "2.7pF")
      (footprint "eagle-import:M(1005)_US(0402)")
      (libsource (lib "eagle-import") (part "CAPACITOR"))
    )
    (comp (ref "C15")
      (value "4.7pF")
      (footprint "eagle-import:M(1005)_US(0402)")
      (libsource (lib "eagle-import") (part "CAPACITOR"))
    )
    (comp (ref "C16")
      (value "47pF")
      (footprint "eagle-import:M(1005)_US(0402)")
      (libsource (lib "eagle-import") (part "CAPACITOR"))
    )
    (comp (ref "C17")
      (value "47pF")
      (footprint "eagle-import:M(1005)_US(0402)")
      (libsource (lib "eagle-import") (part "CAPACITOR"))
    )
    (comp (ref "C18")
      (value "47pF")
      (footprint "eagle-import:M(1005)_US(0402)")
      (libsource (lib "eagle-import") (part "CAPACITOR"))
    )
    (comp (ref "C23")
      (value "15pF")
      (footprint "eagle-import:CAP_(M1005)_0402")
      (libsource (lib "eagle-import") (part "CAP_(M1005)_0402"))
    )
    (comp (ref "C24")
      (value "15pF")
      (footprint "eagle-import:CAP_(M1005)_0402")
      (libsource (lib "eagle-import") (part "CAP_(M1005)_0402"))
    )
    (comp (ref "I1")
      (value "82nH")
      (footprint "eagle-import:M(1608)_US(0603)")
      (libsource (lib "eagle-import") (part "INDUCTOR1608"))
    )
    (comp (ref "IC1")
      (value "SX1278")
      (footprint "eagle-import:SX1278")
      (libsource (lib "eagle-import") (part "SX1278"))
    )
    (comp (ref "L2")
      (value "15nH")
      (footprint "eagle-import:M(1005)_US(0402)")
      (libsource (lib "eagle-import") (part "INDUCTOR"))
    )
    (comp (ref "L3")
      (value "18nH")
      (footprint "eagle-import:M(1005)_US(0402)")
      (libsource (lib "eagle-import") (part "INDUCTOR"))
    )
    (comp (ref "L5")
      (value "12nH")
      (footprint "eagle-import:M(1005)_US(0402)")
      (libsource (lib "eagle-import") (part "INDUCTOR"))
    )
    (comp (ref "Q1")
      (value "NX2520SA-32MHZ")
      (footprint "eagle-import:NX2520SA")
      (libsource (lib "eagle-import") (part "NX2520SA-32MHZ"))
    )
  )
  (nets
    (net (code "1") (name "+3V3") (class "Default")
      (node (ref "C1") (pin "1") (pinfunction "1_1") (pintype "passive"))
      (node (ref "C2") (pin "1") (pinfunction "1_1") (pintype "passive"))
      (node (ref "C22") (pin "1") (pinfunction "1_1") (pintype "passive"))
      (node (ref "C25") (pin "2") (pinfunction "2_2") (pintype "passive"))
      (node (ref "C3") (pin "1") (pinfunction "1_1") (pintype "passive"))
      (node (ref "C34") (pin "2") (pinfunction "2_2") (pintype "passive"))
      (node (ref "C35") (pin "1") (pinfunction "1_1") (pintype "passive"))
      (node (ref "C36") (pin "1") (pinfunction "1_1") (pintype "passive"))
      (node (ref "C38") (pin "1") (pinfunction "1_1") (pintype "passive"))
      (node (ref "C4") (pin "1") (pinfunction "1_1") (pintype "passive"))
      (node (ref "C41") (pin "1") (pinfunction "1_1") (pintype "passive"))
      (node (ref "C42") (pin "1") (pinfunction "1_1") (pintype "passive"))
      (node (ref "C44") (pin "1") (pinfunction "1_1") (pintype "passive"))
      (node (ref "C49") (pin "1") (pinfunction "1_1") (pintype "passive"))
      (node (ref "C50") (pin "1") (pinfunction "1_1") (pintype "passive"))
      (node (ref "C54") (pin "1") (pinfunction "1_1") (pintype "passive"))
      (node (ref "C62") (pin "1") (pinfunction "1_1") (pintype "passive"))
      (node (ref "C67") (pin "1") (pinfunction "1_1") (pintype "passive"))
      (node (ref "C68") (pin "1") (pinfunction "1_1") (pintype "passive"))
      (node (ref "C69") (pin "1") (pinfunction "1_1") (pintype "passive"))
      (node (ref "C7") (pin "1") (pinfunction "1_1") (pintype "passive"))
      (node (ref "IC1") (pin "14") (pinfunction "VBAT_DIG_14") (pintype "bidirectional"))
      (node (ref "IC1") (pin "24") (pinfunction "VBAT_RF_24") (pintype "bidirectional"))
      (node (ref "IC1") (pin "3") (pinfunction "VBAT_ANA_3") (pintype "bidirectional"))
      (node (ref "IC4") (pin "24") (pinfunction "VDD_24") (pintype "bidirectional"))
      (node (ref "IC4") (pin "36") (pinfunction "VDD_36") (pintype "bidirectional"))
      (node (ref "IC4") (pin "48") (pinfunction "VDD_48") (pintype "bidirectional"))
      (node (ref "IC4") (pin "9") (pinfunction "VDD_9") (pintype "bidirectional"))
      (node (ref "R10") (pin "2") (pinfunction "2_2") (pintype "passive"))
      (node (ref "R12") (pin "1") (pinfunction "1_1") (pintype "passive"))
      (node (ref "R21") (pin "2") (pinfunction "2_2") (pintype "passive"))
      (node (ref "R25") (pin "1") (pinfunction "1_1") (pintype "passive"))
      (node (ref "R25") (pin "2") (pinfunction "2_2") (pintype "passive"))
      (node (ref "R36") (pin "1") (pinfunction "1_1") (pintype "passive"))
      (node (ref "R37") (pin "1") (pinfunction "1_1") (pintype "passive"))
      (node (ref "R38") (pin "1") (pinfunction "1_1") (pintype "passive"))
      (node (ref "R39") (pin "1") (pinfunction "1_1") (pintype "passive"))
      (node (ref "R52") (pin "1") (pinfunction "1_1") (pintype "passive"))
      (node (ref "RFSW1") (pin "4") (pinfunction "VDD_4") (pintype "bidirectional"))
      (node (ref "SV2") (pin "4") (pinfunction "4_4") (pintype "passive"))
      (node (ref "SW1") (pin "6") (pinfunction "VDD_6") (pintype "bidirectional"))
      (node (ref "TR2") (pin "10") (pinfunction "D1_10") (pintype "passive"))
      (node (ref "TR2") (pin "7") (pinfunction "D1_7") (pintype "passive"))
      (node (ref "TR2") (pin "8") (pinfunction "D1_8") (pintype "passive"))
      (node (ref "U2") (pin "6") (pinfunction "VOUT_6") (pintype "output"))
      (node (ref "U4") (pin "1") (pinfunction "VDD_RF_1") (pintype "bidirectional"))
      (node (ref "U4") (pin "12") (pinfunction "VDD_D_12") (pintype "bidirectional"))
    )
    (net (code "2") (name "+5V") (class "Default")
      (node (ref "C45") (pin "1") (pinfunction "1_1") (pintype "passive"))
      (node (ref "C46") (pin "1") (pinfunction "1_1") (pintype "passive"))
      (node (ref "C63") (pin "1") (pinfunction "1_1") (pintype "passive"))
      (node (ref "C70") (pin "1") (pinfunction "1_1") (pintype "passive"))
      (node (ref "R8") (pin "2") (pinfunction "2_2") (pintype "passive"))
      (node (ref "TR1") (pin "10") (pinfunction "D1_10") (pintype "passive"))
      (node (ref "TR1") (pin "7") (pinfunction "D1_7") (pintype "passive"))
      (node (ref "TR1") (pin "8") (pinfunction "D1_8") (pintype "passive"))
      (node (ref "U1") (pin "7") (pinfunction "VOUT_7") (pintype "output"))
    )
    (net (code "3") (name "5VB_EN") (class "Default")
      (node (ref "IC4") (pin "42") (pinfunction "CTX1/SCL1/PB6_42") (pintype "bidirectional"))
      (node (ref "R22") (pin "2") (pinfunction "2_2") (pintype "passive"))
      (node (ref "U1") (pin "2") (pinfunction "EN_2") (pintype "input"))
    )
    (net (code "4") (name "AMPIN") (class "Default")
      (node (ref "C18") (pin "2") (pinfunction "2_2") (pintype "passive"))
      (node (ref "C27") (pin "1") (pinfunction "1_1") (pintype "passive"))
    )
    (net (code "5") (name "AMP_3VEN") (class "Default")
      (node (ref "IC4") (pin "2") (pinfunction "PC13_2") (pintype "bidirectional"))
      (node (ref "TR6") (pin "2") (pinfunction "B_2") (pintype "passive"))
    )
    (net (code "6") (name "AMP_5VEN") (class "Default")
      (node (ref "IC4") (pin "41") (pinfunction "CMOSI1/PB5_41") (pintype "bidirectional"))
      (node (ref "TR3") (pin "2") (pinfunction "B_2") (pintype "passive"))
    )
    (net (code "7") (name "CP_DIO_0") (class "Default")
      (node (ref "CN1") (pin "42") (pinfunction "42_42") (pintype "bidirectional"))
      (node (ref "R16") (pin "1") (pinfunction "1_1") (pintype "passive"))
    )
    (net (code "8") (name "CP_DIO_1") (class "Default")
      (node (ref "CN1") (pin "43") (pinfunction "43_43") (pintype "bidirectional"))
      (node (ref "R17") (pin "1") (pinfunction "1_1") (pintype "passive"))
    )
    (net (code "9") (name "CP_DIO_2") (class "Default")
      (node (ref "CN1") (pin "38") (pinfunction "38_38") (pintype "bidirectional"))
      (node (ref "R42") (pin "1") (pinfunction "1_1") (pintype "passive"))
    )
    (net (code "10") (name "CP_UART_RX") (class "Default")
      (node (ref "CN1") (pin "40") (pinfunction "40_40") (pintype "bidirectional"))
      (node (ref "R6") (pin "1") (pinfunction "1_1") (pintype "passive"))
    )
    (net (code "11") (name "CP_UART_TX") (class "Default")
      (node (ref "CN1") (pin "41") (pinfunction "41_41") (pintype "bidirectional"))
      (node (ref "R7") (pin "1") (pinfunction "1_1") (pintype "passive"))
    )
    (net (code "12") (name "DIO0") (class "Default")
      (node (ref "IC1") (pin "8") (pinfunction "DIO0_8") (pintype "bidirectional"))
      (node (ref "IC4") (pin "19") (pinfunction "PB1/AN9_19") (pintype "bidirectional"))
    )
    (net (code "13") (name "DIO1") (class "Default")
      (node (ref "IC1") (pin "9") (pinfunction "DIO1_9") (pintype "bidirectional"))
      (node (ref "IC4") (pin "18") (pinfunction "PB0/AN8_18") (pintype "bidirectional"))
    )
    (net (code "14") (name "DIO2") (class "Default")
      (node (ref "IC1") (pin "10") (pinfunction "DIO2_10") (pintype "bidirectional"))
      (node (ref "IC4") (pin "22") (pinfunction "PB11/SDA2_22") (pintype "bidirectional"))
      (node (ref "R27") (pin "1") (pinfunction "1_1") (pintype "passive"))
    )
    (net (code "15") (name "GATE_V") (class "Default")
      (node (ref "C59") (pin "2") (pinfunction "2_2") (pintype "passive"))
      (node (ref "OCP1") (pin "6") (pinfunction "GATE_6") (pintype "bidirectional"))
      (node (ref "TR4") (pin "3") (pinfunction "G_3") (pintype "passive"))
    )
    (net (code "16") (name "GND") (class "Default")
      (node (ref "C1") (pin "2") (pinfunction "2_2") (pintype "passive"))
      (node (ref "C10") (pin "2") (pinfunction "2_2") (pintype "passive"))
      (node (ref "C12") (pin "2") (pinfunction "2_2") (pintype "passive"))
      (node (ref "C13") (pin "2") (pinfunction "2_2") (pintype "passive"))
      (node (ref "C2") (pin "2") (pinfunction "2_2") (pintype "passive"))
      (node (ref "C20") (pin "1") (pinfunction "1_1") (pintype "passive"))
      (node (ref "C21") (pin "1") (pinfunction "1_1") (pintype "passive"))
      (node (ref "C22") (pin "2") (pinfunction "2_2") (pintype "passive"))
      (node (ref "C23") (pin "1") (pinfunction "1_1") (pintype "passive"))
      (node (ref "C24") (pin "2") (pinfunction "2_2") (pintype "passive"))
      (node (ref "C25") (pin "1") (pinfunction "1_1") (pintype "passive"))
      (node (ref "C26") (pin "2") (pinfunction "2_2") (pintype "passive"))
      (node (ref "C29") (pin "2") (pinfunction "2_2") (pintype "passive"))
      (node (ref "C3") (pin "2") (pinfunction "2_2") (pintype "passive"))
      (node (ref "C30") (pin "1") (pinfunction "1_1") (pintype "passive"))
      (node (ref "C31") (pin "1") (pinfunction "1_1") (pintype "passive"))
      (node (ref "C32") (pin "2") (pinfunction "2_2") (pintype "passive"))
      (node (ref "C34") (pin "1") (pinfunction "1_1") (pintype "passive"))
      (node (ref "C35") (pin "2") (pinfunction "2_2") (pintype "passive"))
      (node (ref "C36") (pin "2") (pinfunction "2_2") (pintype "passive"))
      (node (ref "C37") (pin "2") (pinfunction "2_2") (pintype "passive"))
      (node (ref "C38") (pin "2") (pinfunction "2_2") (pintype "passive"))
      (node (ref "C39") (pin "2") (pinfunction "2_2") (pintype "passive"))
      (node (ref "C4") (pin "2") (pinfunction "2_2") (pintype "passive"))
      (node (ref "C40") (pin "2") (pinfunction "2_2") (pintype "passive"))
      (node (ref "C41") (pin "2") (pinfunction "2_2") (pintype "passive"))
      (node (ref "C42") (pin "2") (pinfunction "2_2") (pintype "passive"))
      (node (ref "C43") (pin "2") (pinfunction "2_2") (pintype "passive"))
      (node (ref "C44") (pin "2") (pinfunction "2_2") (pintype "passive"))
      (node (ref "C45") (pin "2") (pinfunction "2_2") (pintype "passive"))
      (node (ref "C46") (pin "2") (pinfunction "2_2") (pintype "passive"))
      (node (ref "C48") (pin "2") (pinfunction "2_2") (pintype "passive"))
      (node (ref "C49") (pin "2") (pinfunction "2_2") (pintype "passive"))
      (node (ref "C5") (pin "2") (pinfunction "2_2") (pintype "passive"))
      (node (ref "C50") (pin "2") (pinfunction "2_2") (pintype "passive"))
      (node (ref "C53") (pin "2") (pinfunction "2_2") (pintype "passive"))
      (node (ref "C54") (pin "2") (pinfunction "2_2") (pintype "passive"))
      (node (ref "C56") (pin "2") (pinfunction "2_2") (pintype "passive"))
      (node (ref "C57") (pin "2") (pinfunction "2_2") (pintype "passive"))
      (node (ref "C58") (pin "2") (pinfunction "2_2") (pintype "passive"))
      (node (ref "C59") (pin "1") (pinfunction "1_1") (pintype "passive"))
      (node (ref "C6") (pin "2") (pinfunction "2_2") (pintype "passive"))
      (node (ref "C60") (pin "2") (pinfunction "2_2") (pintype "passive"))
      (node (ref "C61") (pin "2") (pinfunction "2_2") (pintype "passive"))
      (node (ref "C62") (pin "2") (pinfunction "2_2") (pintype "passive"))
      (node (ref "C63") (pin "2") (pinfunction "2_2") (pintype "passive"))
      (node (ref "C64") (pin "2") (pinfunction "2_2") (pintype "passive"))
      (node (ref "C65") (pin "2") (pinfunction "2_2") (pintype "passive"))
      (node (ref "C66") (pin "2") (pinfunction "2_2") (pintype "passive"))
      (node (ref "C67") (pin "2") (pinfunction "2_2") (pintype "passive"))
      (node (ref "C68") (pin "2") (pinfunction "2_2") (pintype "passive"))
      (node (ref "C69") (pin "2") (pinfunction "2_2") (pintype "passive"))
      (node (ref "C7") (pin "2") (pinfunction "2_2") (pintype "passive"))
      (node (ref "C70") (pin "2") (pinfunction "2_2") (pintype "passive"))
      (node (ref "C8") (pin "2") (pinfunction "2_2") (pintype "passive"))
      (node (ref "C9") (pin "2") (pinfunction "2_2") (pintype "passive"))
      (node (ref "CN1") (pin "13") (pinfunction "13_13") (pintype "bidirectional"))
      (node (ref "CN1") (pin "14") (pinfunction "14_14") (pintype "bidirectional"))
      (node (ref "CN2") (pin "13") (pinfunction "13_13") (pintype "bidirectional"))
      (node (ref "CN2") (pin "14") (pinfunction "14_14") (pintype "bidirectional"))
      (node (ref "IC1") (pin "15") (pinfunction "GND_15") (pintype "bidirectional"))
      (node (ref "IC1") (pin "21") (pinfunction "GND_21") (pintype "bidirectional"))
      (node (ref "IC1") (pin "22") (pinfunction "GND_22") (pintype "bidirectional"))
      (node (ref "IC1") (pin "23") (pinfunction "GND_23") (pintype "bidirectional"))
      (node (ref "IC1") (pin "26") (pinfunction "GND_26") (pintype "bidirectional"))
      (node (ref "IC1") (pin "29") (pinfunction "GND_29") (pintype "bidirectional"))
      (node (ref "IC3") (pin "2") (pinfunction "GND_2") (pintype "bidirectional"))
      (node (ref "IC3") (pin "4") (pinfunction "GND_4") (pintype "bidirectional"))
      (node (ref "IC4") (pin "23") (pinfunction "VSS_23") (pintype "bidirectional"))
      (node (ref "IC4") (pin "35") (pinfunction "VSS_35") (pintype "bidirectional"))
      (node (ref "IC4") (pin "47") (pinfunction "VSS_47") (pintype "bidirectional"))
      (node (ref "IC4") (pin "8") (pinfunction "VSS_8") (pintype "bidirectional"))
      (node (ref "L3") (pin "2") (pinfunction "2_2") (pintype "passive"))
      (node (ref "MCX7") (pin "2") (pinfunction "2_2") (pintype "bidirectional"))
      (node (ref "MCX7") (pin "3") (pinfunction "2_3") (pintype "bidirectional"))
      (node (ref "MCX7") (pin "4") (pinfunction "2_4") (pintype "bidirectional"))
      (node (ref "MCX7") (pin "5") (pinfunction "2_5") (pintype "bidirectional"))
      (node (ref "OCP1") (pin "1") (pinfunction "GND_1") (pintype "bidirectional"))
      (node (ref "OCP1") (pin "9") (pinfunction "PAD_9") (pintype "bidirectional"))
      (node (ref "Q1") (pin "2") (pinfunction "2_2") (pintype "bidirectional"))
      (node (ref "Q1") (pin "4") (pinfunction "4_4") (pintype "bidirectional"))
      (node (ref "Q2") (pin "2") (pinfunction "G_2") (pintype "bidirectional"))
      (node (ref "Q2") (pin "4") (pinfunction "G_4") (pintype "bidirectional"))
      (node (ref "Q3") (pin "2") (pinfunction "2_2") (pintype "bidirectional"))
      (node (ref "Q3") (pin "4") (pinfunction "4_4") (pintype "bidirectional"))
      (node (ref "R1") (pin "1") (pinfunction "1_1") (pintype "passive"))
      (node (ref "R11") (pin "1") (pinfunction "1_1") (pintype "passive"))
      (node (ref "R14") (pin "2") (pinfunction "2_2") (pintype "passive"))
      (node (ref "R20") (pin "1") (pinfunction "1_1") (pintype "passive"))
      (node (ref "R22") (pin "1") (pinfunction "1_1") (pintype "passive"))
      (node (ref "R23") (pin "1") (pinfunction "1_1") (pintype "passive"))
      (node (ref "R24") (pin "1") (pinfunction "1_1") (pintype "passive"))
      (node (ref "R26") (pin "2") (pinfunction "2_2") (pintype "passive"))
      (node (ref "R32") (pin "1") (pinfunction "1_1") (pintype "passive"))
      (node (ref "R33") (pin "1") (pinfunction "1_1") (pintype "passive"))
      (node (ref "R40") (pin "1") (pinfunction "1_1") (pintype "passive"))
      (node (ref "R41") (pin "1") (pinfunction "1_1") (pintype "passive"))
      (node (ref "R43") (pin "1") (pinfunction "1_1") (pintype "passive"))
      (node (ref "R44") (pin "1") (pinfunction "1_1") (pintype "passive"))
      (node (ref "R45") (pin "1") (pinfunction "1_1") (pintype "passive"))
      (node (ref "R5") (pin "1") (pinfunction "1_1") (pintype "passive"))
      (node (ref "R9") (pin "1") (pinfunction "1_1") (pintype "passive"))
      (node (ref "RF1") (pin "2") (pinfunction "2_2") (pintype "bidirectional"))
      (node (ref "RF1") (pin "3") (pinfunction "2_3") (pintype "bidirectional"))
      (node (ref "RF1") (pin "4") (pinfunction "2_4") (pintype "bidirectional"))
      (node (ref "RF1") (pin "5") (pinfunction "2_5") (pintype "bidirectional"))
      (node (ref "RF2") (pin "2") (pinfunction "2_2") (pintype "bidirectional"))
      (node (ref "RF2") (pin "3") (pinfunction "2_3") (pintype "bidirectional"))
      (node (ref "RF2") (pin "4") (pinfunction "2_4") (pintype "bidirectional"))
      (node (ref "RF2") (pin "5") (pinfunction "2_5") (pintype "bidirectional"))
      (node (ref "RF3") (pin "2") (pinfunction "2_2") (pintype "bidirectional"))
      (node (ref "RF3") (pin "3") (pinfunction "2_3") (pintype "bidirectional"))
      (node (ref "RF3") (pin "4") (pinfunction "2_4") (pintype "bidirectional"))
      (node (ref "RF3") (pin "5") (pinfunction "2_5") (pintype "bidirectional"))
      (node (ref "RF4") (pin "2") (pinfunction "2_2") (pintype "bidirectional"))
      (node (ref "RF4") (pin "3") (pinfunction "2_3") (pintype "bidirectional"))
      (node (ref "RF4") (pin "4") (pinfunction "2_4") (pintype "bidirectional"))
      (node (ref "RF4") (pin "5") (pinfunction "2_5") (pintype "bidirectional"))
      (node (ref "RF5") (pin "2") (pinfunction "2_2") (pintype "bidirectional"))
      (node (ref "RF5") (pin "3") (pinfunction "2_3") (pintype "bidirectional"))
      (node (ref "RF5") (pin "4") (pinfunction "2_4") (pintype "bidirectional"))
      (node (ref "RF5") (pin "5") (pinfunction "2_5") (pintype "bidirectional"))
      (node (ref "RF6") (pin "2") (pinfunction "2_2") (pintype "bidirectional"))
      (node (ref "RF6") (pin "3") (pinfunction "2_3") (pintype "bidirectional"))
      (node (ref "RF6") (pin "4") (pinfunction "2_4") (pintype "bidirectional"))
      (node (ref "RF6") (pin "5") (pinfunction "2_5") (pintype "bidirectional"))
      (node (ref "SV2") (pin "3") (pinfunction "3_3") (pintype "passive"))
      (node (ref "SW1") (pin "10") (pinfunction "GND_10") (pintype "bidirectional"))
      (node (ref "SW1") (pin "12") (pinfunction "GND_12") (pintype "bidirectional"))
      (node (ref "SW1") (pin "13") (pinfunction "PAD_13") (pintype "bidirectional"))
      (node (ref "SW1") (pin "2") (pinfunction "GND_2") (pintype "bidirectional"))
      (node (ref "SW1") (pin "7") (pinfunction "GND_7") (pintype "bidirectional"))
      (node (ref "SW1") (pin "8") (pinfunction "GND_8") (pintype "bidirectional"))
      (node (ref "TR3") (pin "1") (pinfunction "E_1") (pintype "passive"))
      (node (ref "TR5") (pin "1") (pinfunction "E_1") (pintype "passive"))
      (node (ref "TR6") (pin "1") (pinfunction "E_1") (pintype "passive"))
      (node (ref "U1") (pin "6") (pinfunction "GND_6") (pintype "power_in"))
      (node (ref "U2") (pin "11") (pinfunction "EPAD_11") (pintype "passive"))
      (node (ref "U2") (pin "2") (pinfunction "SGND_2") (pintype "power_in"))
      (node (ref "U2") (pin "3") (pinfunction "MODE/SYNC_3") (pintype "passive"))
      (node (ref "U3") (pin "2") (pinfunction "GND_2") (pintype "power_in"))
      (node (ref "U4") (pin "21") (pinfunction "PAD_21") (pintype "bidirectional"))
    )
    (net (code "17") (name "GPIO_0") (class "Default")
      (node (ref "GPIO_0") (pin "1") (pinfunction "1_1") (pintype "bidirectional"))
      (node (ref "U4") (pin "7") (pinfunction "GPIO_0_7") (pintype "bidirectional"))
    )
    (net (code "18") (name "GPIO_1") (class "Default")
      (node (ref "IC4") (pin "27") (pinfunction "MISO2/PB14_27") (pintype "bidirectional"))
      (node (ref "PB14") (pin "1") (pinfunction "1_1") (pintype "bidirectional"))
      (node (ref "U4") (pin "8") (pinfunction "GPIO_1_8") (pintype "bidirectional"))
    )
    (net (code "19") (name "GPIO_2") (class "Default")
      (node (ref "IC4") (pin "26") (pinfunction "SCK2/PB13_26") (pintype "bidirectional"))
      (node (ref "PB13") (pin "1") (pinfunction "1_1") (pintype "bidirectional"))
      (node (ref "U4") (pin "9") (pinfunction "GPIO_2_9") (pintype "bidirectional"))
    )
    (net (code "20") (name "MISO") (class "Default")
      (node (ref "IC1") (pin "17") (pinfunction "MISO_17") (pintype "bidirectional"))
      (node (ref "IC4") (pin "16") (pinfunction "PA6/AN6/MISO1_16") (pintype "bidirectional"))
      (node (ref "U4") (pin "13") (pinfunction "SDO_13") (pintype "bidirectional"))
    )
    (net (code "21") (name "MOSI") (class "Default")
      (node (ref "IC1") (pin "18") (pinfunction "MOSI_18") (pintype "bidirectional"))
      (node (ref "IC4") (pin "17") (pinfunction "PA7/AN7/MOSI1_17") (pintype "bidirectional"))
      (node (ref "U4") (pin "14") (pinfunction "SDI_14") (pintype "bidirectional"))
    )
    (net (code "22") (name "NEWTRX_EN") (class "Default")
      (node (ref "CN1") (pin "37") (pinfunction "37_37") (pintype "bidirectional"))
      (node (ref "TR5") (pin "2") (pinfunction "B_2") (pintype "passive"))
    )
    (net (code "23") (name "NIRQ") (class "Default")
      (node (ref "NIRQ") (pin "1") (pinfunction "1_1") (pintype "bidirectional"))
      (node (ref "U4") (pin "17") (pinfunction "NIRQ_17") (pintype "bidirectional"))
    )
    (net (code "24") (name "NSEL") (class "Default")
      (node (ref "IC4") (pin "28") (pinfunction "MOSI2/PB15_28") (pintype "bidirectional"))
      (node (ref "PB15") (pin "1") (pinfunction "1_1") (pintype "bidirectional"))
      (node (ref "U4") (pin "16") (pinfunction "NSEL_16") (pintype "bidirectional"))
    )
    (net (code "25") (name "NSSL") (class "Default")
      (node (ref "IC1") (pin "19") (pinfunction "NSS_19") (pintype "bidirectional"))
      (node (ref "IC4") (pin "14") (pinfunction "PA4/AN4/NSS1_14") (pintype "bidirectional"))
    )
    (net (code "26") (name "Net-(C11-Pad1)") (class "Default")
      (node (ref "C11") (pin "1") (pinfunction "1_1") (pintype "passive"))
      (node (ref "L2") (pin "2") (pinfunction "2_2") (pintype "passive"))
    )
    (net (code "27") (name "Net-(C11-Pad2)") (class "Default")
      (node (ref "C11") (pin "2") (pinfunction "2_2") (pintype "passive"))
      (node (ref "C12") (pin "1") (pinfunction "1_1") (pintype "passive"))
      (node (ref "C14") (pin "1") (pinfunction "1_1") (pintype "passive"))
      (node (ref "L5") (pin "1") (pinfunction "1_1") (pintype "passive"))
    )
    (net (code "28") (name "Net-(C13-Pad1)") (class "Default")
      (node (ref "C13") (pin "1") (pinfunction "1_1") (pintype "passive"))
      (node (ref "C14") (pin "2") (pinfunction "2_2") (pintype "passive"))
      (node (ref "C17") (pin "1") (pinfunction "1_1") (pintype "passive"))
      (node (ref "L5") (pin "2") (pinfunction "2_2") (pintype "passive"))
    )
    (net (code "29") (name "Net-(C15-Pad2)") (class "Default")
      (node (ref "C15") (pin "2") (pinfunction "2_2") (pintype "passive"))
      (node (ref "C16") (pin "1") (pinfunction "1_1") (pintype "passive"))
    )
    (net (code "30") (name "Net-(C17-Pad2)") (class "Default")
      (node (ref "C17") (pin "2") (pinfunction "2_2") (pintype "passive"))
      (node (ref "C18") (pin "1") (pinfunction "1_1") (pintype "passive"))
    )
    (net (code "31") (name "Net-(C19-Pad1)") (class "Default")
      (node (ref "C19") (pin "1") (pinfunction "1_1") (pintype "passive"))
      (node (ref "C55") (pin "2") (pinfunction "2_2") (pintype "passive"))
      (node (ref "L7") (pin "1") (pinfunction "1_1") (pintype "passive"))
    )
    (net (code "32") (name "Net-(C26-Pad1)") (class "Default")
      (node (ref "C26") (pin "1") (pinfunction "1_1") (pintype "passive"))
      (node (ref "C27") (pin "2") (pinfunction "2_2") (pintype "passive"))
      (node (ref "I5") (pin "1") (pinfunction "1_1") (pintype "passive"))
    )
    (net (code "33") (name "Net-(C28-Pad1)") (class "Default")
      (node (ref "C28") (pin "1") (pinfunction "1_1") (pintype "passive"))
      (node (ref "C29") (pin "1") (pinfunction "1_1") (pintype "passive"))
      (node (ref "I6") (pin "2") (pinfunction "2_2") (pintype "passive"))
    )
    (net (code "34") (name "Net-(C30-Pad2)") (class "Default")
      (node (ref "C30") (pin "2") (pinfunction "2_2") (pintype "passive"))
      (node (ref "C31") (pin "2") (pinfunction "2_2") (pintype "passive"))
      (node (ref "C32") (pin "1") (pinfunction "1_1") (pintype "passive"))
      (node (ref "I7") (pin "1") (pinfunction "1_1") (pintype "passive"))
      (node (ref "R1") (pin "2") (pinfunction "2_2") (pintype "passive"))
      (node (ref "TR1") (pin "5") (pinfunction "D2_5") (pintype "passive"))
      (node (ref "TR1") (pin "6") (pinfunction "D2_6") (pintype "passive"))
      (node (ref "TR1") (pin "9") (pinfunction "D2_9") (pintype "passive"))
      (node (ref "TR2") (pin "5") (pinfunction "D2_5") (pintype "passive"))
      (node (ref "TR2") (pin "6") (pinfunction "D2_6") (pintype "passive"))
      (node (ref "TR2") (pin "9") (pinfunction "D2_9") (pintype "passive"))
    )
    (net (code "35") (name "Net-(C51-Pad2)") (class "Default")
      (node (ref "C51") (pin "2") (pinfunction "2_2") (pintype "passive"))
      (node (ref "R12") (pin "2") (pinfunction "2_2") (pintype "passive"))
    )
    (net (code "36") (name "Net-(C52-Pad1)") (class "Default")
      (node (ref "C52") (pin "1") (pinfunction "1_1") (pintype "passive"))
      (node (ref "R13") (pin "1") (pinfunction "1_1") (pintype "passive"))
    )
    (net (code "37") (name "Net-(CN2-Pad25)") (class "Default")
      (node (ref "CN2") (pin "25") (pinfunction "25_25") (pintype "bidirectional"))
      (node (ref "CN2") (pin "26") (pinfunction "26_26") (pintype "bidirectional"))
      (node (ref "R52") (pin "2") (pinfunction "2_2") (pintype "passive"))
    )
    (net (code "38") (name "Net-(I5-Pad2)") (class "Default")
      (node (ref "I5") (pin "2") (pinfunction "2_2") (pintype "passive"))
      (node (ref "R2") (pin "1") (pinfunction "1_1") (pintype "passive"))
    )
    (net (code "39") (name "Net-(IC1-VR_ANA)") (class "Default")
      (node (ref "C5") (pin "1") (pinfunction "1_1") (pintype "passive"))
      (node (ref "IC1") (pin "2") (pinfunction "VR_ANA_2") (pintype "bidirectional"))
    )
    (net (code "40") (name "Net-(IC1-VR_DIG)") (class "Default")
      (node (ref "C6") (pin "1") (pinfunction "1_1") (pintype "passive"))
      (node (ref "IC1") (pin "4") (pinfunction "VR_DIG_4") (pintype "bidirectional"))
    )
    (net (code "41") (name "Net-(IC1-VR_PA)") (class "Default")
      (node (ref "C8") (pin "1") (pinfunction "1_1") (pintype "passive"))
      (node (ref "C9") (pin "1") (pinfunction "1_1") (pintype "passive"))
      (node (ref "I1") (pin "1") (pinfunction "1_1") (pintype "passive"))
      (node (ref "IC1") (pin "25") (pinfunction "VR_PA_25") (pintype "bidirectional"))
    )
    (net (code "42") (name "Net-(IC3-RFIN)") (class "Default")
      (node (ref "IC3") (pin "1") (pinfunction "RFIN_1") (pintype "bidirectional"))
      (node (ref "R2") (pin "2") (pinfunction "2_2") (pintype "passive"))
    )
    (net (code "43") (name "Net-(IC3-RFOUT)") (class "Default")
      (node (ref "I6") (pin "1") (pinfunction "1_1") (pintype "passive"))
      (node (ref "I7") (pin "2") (pinfunction "2_2") (pintype "passive"))
      (node (ref "IC3") (pin "3") (pinfunction "RFOUT_3") (pintype "bidirectional"))
    )
    (net (code "44") (name "Net-(IC4-BOOT0)") (class "Default")
      (node (ref "IC4") (pin "44") (pinfunction "BOOT0_44") (pintype "bidirectional"))
      (node (ref "R19") (pin "1") (pinfunction "1_1") (pintype "passive"))
    )
    (net (code "45") (name "Net-(IC4-CANRX{slash}PB8)") (class "Default")
      (node (ref "IC4") (pin "45") (pinfunction "CANRX/PB8_45") (pintype "bidirectional"))
      (node (ref "PB8") (pin "1") (pinfunction "1_1") (pintype "bidirectional"))
    )
    (net (code "46") (name "Net-(IC4-CANTX{slash}PB9)") (class "Default")
      (node (ref "IC4") (pin "46") (pinfunction "CANTX/PB9_46") (pintype "bidirectional"))
      (node (ref "R41") (pin "2") (pinfunction "2_2") (pintype "passive"))
      (node (ref "R42") (pin "2") (pinfunction "2_2") (pintype "passive"))
    )
    (net (code "47") (name "Net-(IC4-CNSS1{slash}PA15)") (class "Default")
      (node (ref "IC4") (pin "38") (pinfunction "CNSS1/PA15_38") (pintype "bidirectional"))
      (node (ref "R30") (pin "2") (pinfunction "2_2") (pintype "passive"))
    )
    (net (code "48") (name "Net-(IC4-CRX1{slash}SDA1{slash}PB7)") (class "Default")
      (node (ref "IC4") (pin "43") (pinfunction "CRX1/SDA1/PB7_43") (pintype "bidirectional"))
      (node (ref "PB7") (pin "1") (pinfunction "1_1") (pintype "bidirectional"))
    )
    (net (code "49") (name "Net-(IC4-CSCK1{slash}PB3)") (class "Default")
      (node (ref "IC4") (pin "39") (pinfunction "CSCK1/PB3_39") (pintype "bidirectional"))
      (node (ref "R31") (pin "2") (pinfunction "2_2") (pintype "passive"))
    )
    (net (code "50") (name "Net-(IC4-D+{slash}PA12)") (class "Default")
      (node (ref "IC4") (pin "33") (pinfunction "D+/PA12_33") (pintype "bidirectional"))
      (node (ref "R27") (pin "2") (pinfunction "2_2") (pintype "passive"))
    )
    (net (code "51") (name "Net-(IC4-OSCIN)") (class "Default")
      (node (ref "C39") (pin "1") (pinfunction "1_1") (pintype "passive"))
      (node (ref "IC4") (pin "5") (pinfunction "OSCIN_5") (pintype "bidirectional"))
      (node (ref "Q2") (pin "1") (pinfunction "I_1") (pintype "bidirectional"))
      (node (ref "R18") (pin "2") (pinfunction "2_2") (pintype "passive"))
    )
    (net (code "52") (name "Net-(IC4-OSCOUNT)") (class "Default")
      (node (ref "C40") (pin "1") (pinfunction "1_1") (pintype "passive"))
      (node (ref "IC4") (pin "6") (pinfunction "OSCOUNT_6") (pintype "bidirectional"))
      (node (ref "Q2") (pin "3") (pinfunction "O_3") (pintype "bidirectional"))
      (node (ref "R18") (pin "1") (pinfunction "1_1") (pintype "passive"))
    )
    (net (code "53") (name "Net-(IC4-PA0{slash}AN0)") (class "Default")
      (node (ref "IC4") (pin "10") (pinfunction "PA0/AN0_10") (pintype "bidirectional"))
      (node (ref "R16") (pin "2") (pinfunction "2_2") (pintype "passive"))
      (node (ref "R23") (pin "2") (pinfunction "2_2") (pintype "passive"))
    )
    (net (code "54") (name "Net-(IC4-PA1{slash}AN1)") (class "Default")
      (node (ref "IC4") (pin "11") (pinfunction "PA1/AN1_11") (pintype "bidirectional"))
      (node (ref "R17") (pin "2") (pinfunction "2_2") (pintype "passive"))
      (node (ref "R24") (pin "2") (pinfunction "2_2") (pintype "passive"))
    )
    (net (code "55") (name "Net-(IC4-PA2{slash}AN2{slash}TX2)") (class "Default")
      (node (ref "IC4") (pin "12") (pinfunction "PA2/AN2/TX2_12") (pintype "bidirectional"))
      (node (ref "R7") (pin "2") (pinfunction "2_2") (pintype "passive"))
    )
    (net (code "56") (name "Net-(IC4-PA3{slash}AN3{slash}RX2)") (class "Default")
      (node (ref "IC4") (pin "13") (pinfunction "PA3/AN3/RX2_13") (pintype "bidirectional"))
      (node (ref "R6") (pin "2") (pinfunction "2_2") (pintype "passive"))
    )
    (net (code "57") (name "Net-(IC4-PA8)") (class "Default")
      (node (ref "IC4") (pin "29") (pinfunction "PA8_29") (pintype "bidirectional"))
      (node (ref "R34") (pin "2") (pinfunction "2_2") (pintype "passive"))
    )
    (net (code "58") (name "Net-(IC4-PB2{slash}BOOT1)") (class "Default")
      (node (ref "IC4") (pin "20") (pinfunction "PB2/BOOT1_20") (pintype "bidirectional"))
      (node (ref "R5") (pin "2") (pinfunction "2_2") (pintype "passive"))
    )
    (net (code "59") (name "Net-(IC4-SWCLK)") (class "Default")
      (node (ref "IC4") (pin "37") (pinfunction "SWCLK_37") (pintype "bidirectional"))
      (node (ref "SWCLK") (pin "1") (pinfunction "1_1") (pintype "bidirectional"))
    )
    (net (code "60") (name "Net-(IC4-SWIO)") (class "Default")
      (node (ref "IC4") (pin "34") (pinfunction "SWIO_34") (pintype "bidirectional"))
      (node (ref "SWIO") (pin "1") (pinfunction "1_1") (pintype "bidirectional"))
    )
    (net (code "61") (name "Net-(IC4-VBAT)") (class "Default")
      (node (ref "IC4") (pin "1") (pinfunction "VBAT_1") (pintype "bidirectional"))
      (node (ref "VBAT") (pin "1") (pinfunction "1_1") (pintype "bidirectional"))
    )
    (net (code "62") (name "Net-(OCP1-SENSE)") (class "Default")
      (node (ref "C57") (pin "1") (pinfunction "1_1") (pintype "passive"))
      (node (ref "C58") (pin "1") (pinfunction "1_1") (pintype "passive"))
      (node (ref "OCP1") (pin "7") (pinfunction "SENSE_7") (pintype "bidirectional"))
      (node (ref "R28") (pin "2") (pinfunction "2_2") (pintype "passive"))
      (node (ref "TR4") (pin "1") (pinfunction "D_1") (pintype "passive"))
      (node (ref "TR4") (pin "2") (pinfunction "D_2") (pintype "passive"))
      (node (ref "TR4") (pin "5") (pinfunction "D_5") (pintype "passive"))
      (node (ref "TR4") (pin "6") (pinfunction "D_6") (pintype "passive"))
      (node (ref "TR4") (pin "7") (pinfunction "D_7") (pintype "passive"))
    )
    (net (code "63") (name "Net-(OCP1-~{ON})") (class "Default")
      (node (ref "OCP1") (pin "4") (pinfunction "~{ON}_4") (pintype "bidirectional"))
      (node (ref "R29") (pin "1") (pinfunction "1_1") (pintype "passive"))
      (node (ref "TR5") (pin "3") (pinfunction "C_3") (pintype "passive"))
    )
    (net (code "64") (name "Net-(R46-Pad1)") (class "Default")
      (node (ref "R46") (pin "1") (pinfunction "1_1") (pintype "passive"))
      (node (ref "R49") (pin "2") (pinfunction "2_2") (pintype "passive"))
    )
    (net (code "65") (name "Net-(R47-Pad1)") (class "Default")
      (node (ref "R47") (pin "1") (pinfunction "1_1") (pintype "passive"))
      (node (ref "R50") (pin "2") (pinfunction "2_2") (pintype "passive"))
    )
    (net (code "66") (name "Net-(R48-Pad1)") (class "Default")
      (node (ref "R48") (pin "1") (pinfunction "1_1") (pintype "passive"))
      (node (ref "R51") (pin "2") (pinfunction "2_2") (pintype "passive"))
    )
    (net (code "67") (name "Net-(RFSW1-ANT)") (class "Default")
      (node (ref "MCX7") (pin "1") (pinfunction "1_1") (pintype "bidirectional"))
      (node (ref "RFSW1") (pin "13") (pinfunction "ANT_13") (pintype "bidirectional"))
    )
    (net (code "68") (name "Net-(RFSW1-RF1)") (class "Default")
      (node (ref "RF1") (pin "1") (pinfunction "1_1") (pintype "bidirectional"))
      (node (ref "RFSW1") (pin "3") (pinfunction "RF1_3") (pintype "bidirectional"))
    )
    (net (code "69") (name "Net-(RFSW1-RF2)") (class "Default")
      (node (ref "RF2") (pin "1") (pinfunction "1_1") (pintype "bidirectional"))
      (node (ref "RFSW1") (pin "9") (pinfunction "RF2_9") (pintype "bidirectional"))
    )
    (net (code "70") (name "Net-(RFSW1-RF3)") (class "Default")
      (node (ref "RF3") (pin "1") (pinfunction "1_1") (pintype "bidirectional"))
      (node (ref "RFSW1") (pin "2") (pinfunction "RF3_2") (pintype "bidirectional"))
    )
    (net (code "71") (name "Net-(RFSW1-RF4)") (class "Default")
      (node (ref "RF4") (pin "1") (pinfunction "1_1") (pintype "bidirectional"))
      (node (ref "RFSW1") (pin "10") (pinfunction "RF4_10") (pintype "bidirectional"))
    )
    (net (code "72") (name "Net-(RFSW1-RF5)") (class "Default")
      (node (ref "RF5") (pin "1") (pinfunction "1_1") (pintype "bidirectional"))
      (node (ref "RFSW1") (pin "1") (pinfunction "RF5_1") (pintype "bidirectional"))
    )
    (net (code "73") (name "Net-(RFSW1-RF6)") (class "Default")
      (node (ref "RF6") (pin "1") (pinfunction "1_1") (pintype "bidirectional"))
      (node (ref "RFSW1") (pin "11") (pinfunction "RF6_11") (pintype "bidirectional"))
    )
    (net (code "74") (name "Net-(RFSW1-V1)") (class "Default")
      (node (ref "C66") (pin "1") (pinfunction "1_1") (pintype "passive"))
      (node (ref "R45") (pin "2") (pinfunction "2_2") (pintype "passive"))
      (node (ref "R48") (pin "2") (pinfunction "2_2") (pintype "passive"))
      (node (ref "RFSW1") (pin "7") (pinfunction "V1_7") (pintype "bidirectional"))
    )
    (net (code "75") (name "Net-(RFSW1-V2)") (class "Default")
      (node (ref "C65") (pin "1") (pinfunction "1_1") (pintype "passive"))
      (node (ref "R44") (pin "2") (pinfunction "2_2") (pintype "passive"))
      (node (ref "R47") (pin "2") (pinfunction "2_2") (pintype "passive"))
      (node (ref "RFSW1") (pin "6") (pinfunction "V2_6") (pintype "bidirectional"))
    )
    (net (code "76") (name "Net-(RFSW1-V3)") (class "Default")
      (node (ref "C64") (pin "1") (pinfunction "1_1") (pintype "passive"))
      (node (ref "R43") (pin "2") (pinfunction "2_2") (pintype "passive"))
      (node (ref "R46") (pin "2") (pinfunction "2_2") (pintype "passive"))
      (node (ref "RFSW1") (pin "5") (pinfunction "V3_5") (pintype "bidirectional"))
    )
    (net (code "77") (name "Net-(SW1-J2)") (class "Default")
      (node (ref "C28") (pin "2") (pinfunction "2_2") (pintype "passive"))
      (node (ref "SW1") (pin "9") (pinfunction "J2_9") (pintype "bidirectional"))
    )
    (net (code "78") (name "Net-(SW1-RFC)") (class "Default")
      (node (ref "C33") (pin "1") (pinfunction "1_1") (pintype "passive"))
      (node (ref "SW1") (pin "11") (pinfunction "RFC_11") (pintype "bidirectional"))
    )
    (net (code "79") (name "Net-(TR1-G1)") (class "Default")
      (node (ref "R4") (pin "1") (pinfunction "1_1") (pintype "passive"))
      (node (ref "TR1") (pin "2") (pinfunction "G1_2") (pintype "passive"))
      (node (ref "TR1") (pin "4") (pinfunction "G2_4") (pintype "passive"))
      (node (ref "TR3") (pin "3") (pinfunction "C_3") (pintype "passive"))
    )
    (net (code "80") (name "Net-(TR1-S1)") (class "Default")
      (node (ref "R4") (pin "2") (pinfunction "2_2") (pintype "passive"))
      (node (ref "TR1") (pin "1") (pinfunction "S1_1") (pintype "passive"))
      (node (ref "TR1") (pin "3") (pinfunction "S2_3") (pintype "passive"))
    )
    (net (code "81") (name "Net-(TR2-G1)") (class "Default")
      (node (ref "R3") (pin "1") (pinfunction "1_1") (pintype "passive"))
      (node (ref "TR2") (pin "2") (pinfunction "G1_2") (pintype "passive"))
      (node (ref "TR2") (pin "4") (pinfunction "G2_4") (pintype "passive"))
      (node (ref "TR6") (pin "3") (pinfunction "C_3") (pintype "passive"))
    )
    (net (code "82") (name "Net-(TR2-S1)") (class "Default")
      (node (ref "R3") (pin "2") (pinfunction "2_2") (pintype "passive"))
      (node (ref "TR2") (pin "1") (pinfunction "S1_1") (pintype "passive"))
      (node (ref "TR2") (pin "3") (pinfunction "S2_3") (pintype "passive"))
    )
    (net (code "83") (name "Net-(U1-CBST)") (class "Default")
      (node (ref "C47") (pin "2") (pinfunction "2_2") (pintype "passive"))
      (node (ref "U1") (pin "1") (pinfunction "CBST_1") (pintype "passive"))
    )
    (net (code "84") (name "Net-(U1-FB)") (class "Default")
      (node (ref "R8") (pin "1") (pinfunction "1_1") (pintype "passive"))
      (node (ref "R9") (pin "2") (pinfunction "2_2") (pintype "passive"))
      (node (ref "U1") (pin "3") (pinfunction "FB_3") (pintype "input"))
    )
    (net (code "85") (name "Net-(U1-SW)") (class "Default")
      (node (ref "C47") (pin "1") (pinfunction "1_1") (pintype "passive"))
      (node (ref "L4") (pin "1") (pinfunction "1_1") (pintype "passive"))
      (node (ref "U1") (pin "5") (pinfunction "SW_5") (pintype "passive"))
    )
    (net (code "86") (name "Net-(U2-*SHDN)") (class "Default")
      (node (ref "R15") (pin "2") (pinfunction "2_2") (pintype "passive"))
      (node (ref "U2") (pin "8") (pinfunction "*SHDN_8") (pintype "input"))
    )
    (net (code "87") (name "Net-(U2-FB)") (class "Default")
      (node (ref "C51") (pin "1") (pinfunction "1_1") (pintype "passive"))
      (node (ref "C52") (pin "2") (pinfunction "2_2") (pintype "passive"))
      (node (ref "R10") (pin "1") (pinfunction "1_1") (pintype "passive"))
      (node (ref "R11") (pin "2") (pinfunction "2_2") (pintype "passive"))
      (node (ref "U2") (pin "9") (pinfunction "FB_9") (pintype "output"))
    )
    (net (code "88") (name "Net-(U2-RT)") (class "Default")
      (node (ref "R14") (pin "1") (pinfunction "1_1") (pintype "passive"))
      (node (ref "U2") (pin "1") (pinfunction "RT_1") (pintype "input"))
    )
    (net (code "89") (name "Net-(U2-SW1)") (class "Default")
      (node (ref "L1") (pin "1") (pinfunction "1_1") (pintype "passive"))
      (node (ref "U2") (pin "4") (pinfunction "SW1_4") (pintype "passive"))
    )
    (net (code "90") (name "Net-(U2-SW2)") (class "Default")
      (node (ref "L1") (pin "2") (pinfunction "2_2") (pintype "passive"))
      (node (ref "U2") (pin "5") (pinfunction "SW2_5") (pintype "passive"))
    )
    (net (code "91") (name "Net-(U2-VC)") (class "Default")
      (node (ref "R13") (pin "2") (pinfunction "2_2") (pintype "passive"))
      (node (ref "U2") (pin "10") (pinfunction "VC_10") (pintype "output"))
    )
    (net (code "92") (name "Net-(U3-SET0)") (class "Default")
      (node (ref "R39") (pin "2") (pinfunction "2_2") (pintype "passive"))
      (node (ref "R40") (pin "2") (pinfunction "2_2") (pintype "passive"))
      (node (ref "U3") (pin "4") (pinfunction "SET0_4") (pintype "input"))
    )
    (net (code "93") (name "Net-(U3-SET1)") (class "Default")
      (node (ref "R38") (pin "2") (pinfunction "2_2") (pintype "passive"))
      (node (ref "U3") (pin "5") (pinfunction "SET1_5") (pintype "input"))
    )
    (net (code "94") (name "Net-(U3-SET2)") (class "Default")
      (node (ref "R37") (pin "2") (pinfunction "2_2") (pintype "passive"))
      (node (ref "U3") (pin "6") (pinfunction "SET2_6") (pintype "input"))
    )
    (net (code "95") (name "Net-(U3-VCC)") (class "Default")
      (node (ref "C61") (pin "1") (pinfunction "1_1") (pintype "passive"))
      (node (ref "R34") (pin "1") (pinfunction "1_1") (pintype "passive"))
      (node (ref "R36") (pin "2") (pinfunction "2_2") (pintype "passive"))
      (node (ref "U3") (pin "8") (pinfunction "VCC_8") (pintype "power_in"))
    )
    (net (code "96") (name "Net-(U3-~{WDO})") (class "Default")
      (node (ref "R35") (pin "2") (pinfunction "2_2") (pintype "passive"))
      (node (ref "U3") (pin "7") (pinfunction "~{WDO}_7") (pintype "output"))
    )
    (net (code "97") (name "Net-(U4-RF_P)") (class "Default")
      (node (ref "C19") (pin "2") (pinfunction "2_2") (pintype "passive"))
      (node (ref "L6") (pin "2") (pinfunction "2_2") (pintype "passive"))
      (node (ref "U4") (pin "3") (pinfunction "RF_P_3") (pintype "bidirectional"))
    )
    (net (code "98") (name "Net-(U4-RX_N)") (class "Default")
      (node (ref "C20") (pin "2") (pinfunction "2_2") (pintype "passive"))
      (node (ref "L6") (pin "1") (pinfunction "1_1") (pintype "passive"))
      (node (ref "L7") (pin "2") (pinfunction "2_2") (pintype "passive"))
      (node (ref "U4") (pin "4") (pinfunction "RX_N_4") (pintype "bidirectional"))
    )
    (net (code "99") (name "Net-(U4-VR_DIG)") (class "Default")
      (node (ref "C21") (pin "2") (pinfunction "2_2") (pintype "passive"))
      (node (ref "U4") (pin "10") (pinfunction "VR_DIG_10") (pintype "bidirectional"))
    )
    (net (code "100") (name "PROG_BOOT0") (class "Default")
      (node (ref "CN1") (pin "3") (pinfunction "3_3") (pintype "bidirectional"))
      (node (ref "R19") (pin "2") (pinfunction "2_2") (pintype "passive"))
      (node (ref "R20") (pin "2") (pinfunction "2_2") (pintype "passive"))
      (node (ref "SV2") (pin "6") (pinfunction "6_6") (pintype "passive"))
    )
    (net (code "101") (name "PROG_RST") (class "Default")
      (node (ref "CN1") (pin "4") (pinfunction "4_4") (pintype "bidirectional"))
      (node (ref "IC4") (pin "7") (pinfunction "~{RESET}_7") (pintype "bidirectional"))
      (node (ref "R21") (pin "1") (pinfunction "1_1") (pintype "passive"))
      (node (ref "R35") (pin "1") (pinfunction "1_1") (pintype "passive"))
      (node (ref "SV2") (pin "5") (pinfunction "5_5") (pintype "passive"))
    )
    (net (code "102") (name "PROG_RX") (class "Default")
      (node (ref "CN1") (pin "1") (pinfunction "1_1") (pintype "bidirectional"))
      (node (ref "IC4") (pin "31") (pinfunction "RX1/PA10_31") (pintype "bidirectional"))
      (node (ref "SV2") (pin "2") (pinfunction "2_2") (pintype "passive"))
    )
    (net (code "103") (name "PROG_TX") (class "Default")
      (node (ref "CN1") (pin "2") (pinfunction "2_2") (pintype "bidirectional"))
      (node (ref "IC4") (pin "30") (pinfunction "TX1/PA9_30") (pintype "bidirectional"))
      (node (ref "SV2") (pin "1") (pinfunction "1_1") (pintype "passive"))
    )
    (net (code "104") (name "RFI") (class "Default")
      (node (ref "C15") (pin "1") (pinfunction "1_1") (pintype "passive"))
      (node (ref "IC1") (pin "1") (pinfunction "RFI_LF_1") (pintype "bidirectional"))
      (node (ref "L3") (pin "1") (pinfunction "1_1") (pintype "passive"))
    )
    (net (code "105") (name "RFO") (class "Default")
      (node (ref "C10") (pin "1") (pinfunction "1_1") (pintype "passive"))
      (node (ref "I1") (pin "2") (pinfunction "2_2") (pintype "passive"))
      (node (ref "IC1") (pin "28") (pinfunction "RFO_LF_28") (pintype "bidirectional"))
      (node (ref "L2") (pin "1") (pinfunction "1_1") (pintype "passive"))
    )
    (net (code "106") (name "RFSW_V1") (class "Default")
      (node (ref "C43") (pin "1") (pinfunction "1_1") (pintype "passive"))
      (node (ref "R31") (pin "1") (pinfunction "1_1") (pintype "passive"))
      (node (ref "R33") (pin "2") (pinfunction "2_2") (pintype "passive"))
      (node (ref "SW1") (pin "4") (pinfunction "V1_4") (pintype "bidirectional"))
    )
    (net (code "107") (name "RFSW_V2") (class "Default")
      (node (ref "C37") (pin "1") (pinfunction "1_1") (pintype "passive"))
      (node (ref "R30") (pin "1") (pinfunction "1_1") (pintype "passive"))
      (node (ref "R32") (pin "2") (pinfunction "2_2") (pintype "passive"))
      (node (ref "SW1") (pin "5") (pinfunction "V2_5") (pintype "bidirectional"))
    )
    (net (code "108") (name "RF_RX") (class "Default")
      (node (ref "C16") (pin "2") (pinfunction "2_2") (pintype "passive"))
      (node (ref "SW1") (pin "3") (pinfunction "P3_3") (pintype "bidirectional"))
    )
    (net (code "109") (name "RST_L") (class "Default")
      (node (ref "IC1") (pin "7") (pinfunction "NRESET_7") (pintype "bidirectional"))
      (node (ref "IC4") (pin "21") (pinfunction "PB10/SCL2_21") (pintype "bidirectional"))
    )
    (net (code "110") (name "SCK") (class "Default")
      (node (ref "IC1") (pin "16") (pinfunction "SCK_16") (pintype "bidirectional"))
      (node (ref "IC4") (pin "15") (pinfunction "PA5/AN5/SCK1_15") (pintype "bidirectional"))
      (node (ref "U4") (pin "15") (pinfunction "SCLK_15") (pintype "bidirectional"))
    )
    (net (code "111") (name "SI_RX") (class "Default")
      (node (ref "C55") (pin "1") (pinfunction "1_1") (pintype "passive"))
      (node (ref "SW1") (pin "1") (pinfunction "P1_1") (pintype "bidirectional"))
    )
    (net (code "112") (name "SI_SDN") (class "Default")
      (node (ref "IC4") (pin "25") (pinfunction "NSS2/PB12_25") (pintype "bidirectional"))
      (node (ref "PB12") (pin "1") (pinfunction "1_1") (pintype "bidirectional"))
      (node (ref "R26") (pin "1") (pinfunction "1_1") (pintype "passive"))
      (node (ref "U4") (pin "20") (pinfunction "SDN_20") (pintype "bidirectional"))
    )
    (net (code "113") (name "TOANT") (class "Default")
      (node (ref "C33") (pin "2") (pinfunction "2_2") (pintype "passive"))
      (node (ref "TP14") (pin "1") (pinfunction "1_1") (pintype "bidirectional"))
    )
    (net (code "114") (name "UNR") (class "Default")
      (node (ref "C48") (pin "1") (pinfunction "1_1") (pintype "passive"))
      (node (ref "C53") (pin "1") (pinfunction "1_1") (pintype "passive"))
      (node (ref "C56") (pin "1") (pinfunction "1_1") (pintype "passive"))
      (node (ref "C60") (pin "1") (pinfunction "1_1") (pintype "passive"))
      (node (ref "L4") (pin "2") (pinfunction "2_2") (pintype "passive"))
      (node (ref "OCP1") (pin "3") (pinfunction "OUT_3") (pintype "bidirectional"))
      (node (ref "R15") (pin "1") (pinfunction "1_1") (pintype "passive"))
      (node (ref "TR4") (pin "4") (pinfunction "S_4") (pintype "passive"))
      (node (ref "TR4") (pin "8") (pinfunction "S_8") (pintype "passive"))
      (node (ref "U1") (pin "4") (pinfunction "VIN_4") (pintype "input"))
      (node (ref "U2") (pin "7") (pinfunction "VIN_7") (pintype "input"))
    )
    (net (code "115") (name "UNREG1") (class "Default")
      (node (ref "CN1") (pin "23") (pinfunction "23_23") (pintype "bidirectional"))
      (node (ref "CN1") (pin "24") (pinfunction "24_24") (pintype "bidirectional"))
      (node (ref "OCP1") (pin "8") (pinfunction "IN_8") (pintype "bidirectional"))
      (node (ref "R28") (pin "1") (pinfunction "1_1") (pintype "passive"))
      (node (ref "R29") (pin "2") (pinfunction "2_2") (pintype "passive"))
    )
    (net (code "116") (name "V1") (class "Default")
      (node (ref "CN2") (pin "27") (pinfunction "27_27") (pintype "bidirectional"))
      (node (ref "R51") (pin "1") (pinfunction "1_1") (pintype "passive"))
    )
    (net (code "117") (name "V2") (class "Default")
      (node (ref "CN2") (pin "28") (pinfunction "28_28") (pintype "bidirectional"))
      (node (ref "R50") (pin "1") (pinfunction "1_1") (pintype "passive"))
    )
    (net (code "118") (name "V3") (class "Default")
      (node (ref "CN2") (pin "29") (pinfunction "29_29") (pintype "bidirectional"))
      (node (ref "R49") (pin "1") (pinfunction "1_1") (pintype "passive"))
    )
    (net (code "119") (name "WDI") (class "Default")
      (node (ref "IC4") (pin "32") (pinfunction "D-/PA11_32") (pintype "bidirectional"))
      (node (ref "U3") (pin "1") (pinfunction "WDI_1") (pintype "input"))
    )
    (net (code "120") (name "XIN") (class "Default")
      (node (ref "Q3") (pin "3") (pinfunction "3_3") (pintype "bidirectional"))
      (node (ref "U4") (pin "19") (pinfunction "XIN_19") (pintype "bidirectional"))
    )
    (net (code "121") (name "XOUT") (class "Default")
      (node (ref "Q3") (pin "1") (pinfunction "1_1") (pintype "bidirectional"))
      (node (ref "U4") (pin "18") (pinfunction "XOUT_18") (pintype "bidirectional"))
    )
    (net (code "122") (name "XTA") (class "Default")
      (node (ref "C24") (pin "1") (pinfunction "1_1") (pintype "passive"))
      (node (ref "IC1") (pin "5") (pinfunction "XTA_5") (pintype "bidirectional"))
      (node (ref "Q1") (pin "3") (pinfunction "3_3") (pintype "bidirectional"))
    )
    (net (code "123") (name "XTB") (class "Default")
      (node (ref "C23") (pin "2") (pinfunction "2_2") (pintype "passive"))
      (node (ref "IC1") (pin "6") (pinfunction "XTB_6") (pintype "bidirectional"))
      (node (ref "Q1") (pin "1") (pinfunction "1_1") (pintype "bidirectional"))
    )
    (net (code "124") (name "unconnected-(CN1-Pad5)") (class "Default")
      (node (ref "CN1") (pin "5") (pinfunction "5_5") (pintype "bidirectional"))
    )
    (net (code "125") (name "unconnected-(CN1-Pad6)") (class "Default")
      (node (ref "CN1") (pin "6") (pinfunction "6_6") (pintype "bidirectional"))
    )
    (net (code "126") (name "unconnected-(CN1-Pad7)") (class "Default")
      (node (ref "CN1") (pin "7") (pinfunction "7_7") (pintype "bidirectional"))
    )
    (net (code "127") (name "unconnected-(CN1-Pad8)") (class "Default")
      (node (ref "CN1") (pin "8") (pinfunction "8_8") (pintype "bidirectional"))
    )
    (net (code "128") (name "unconnected-(CN1-Pad9)") (class "Default")
      (node (ref "CN1") (pin "9") (pinfunction "9_9") (pintype "bidirectional"))
    )
    (net (code "129") (name "unconnected-(CN1-Pad10)") (class "Default")
      (node (ref "CN1") (pin "10") (pinfunction "10_10") (pintype "bidirectional"))
    )
    (net (code "130") (name "unconnected-(CN1-Pad11)") (class "Default")
      (node (ref "CN1") (pin "11") (pinfunction "11_11") (pintype "bidirectional"))
    )
    (net (code "131") (name "unconnected-(CN1-Pad12)") (class "Default")
      (node (ref "CN1") (pin "12") (pinfunction "12_12") (pintype "bidirectional"))
    )
    (net (code "132") (name "unconnected-(CN1-Pad15)") (class "Default")
      (node (ref "CN1") (pin "15") (pinfunction "15_15") (pintype "bidirectional"))
    )
    (net (code "133") (name "unconnected-(CN1-Pad16)") (class "Default")
      (node (ref "CN1") (pin "16") (pinfunction "16_16") (pintype "bidirectional"))
    )
    (net (code "134") (name "unconnected-(CN1-Pad17)") (class "Default")
      (node (ref "CN1") (pin "17") (pinfunction "17_17") (pintype "bidirectional"))
    )
    (net (code "135") (name "unconnected-(CN1-Pad18)") (class "Default")
      (node (ref "CN1") (pin "18") (pinfunction "18_18") (pintype "bidirectional"))
    )
    (net (code "136") (name "unconnected-(CN1-Pad19)") (class "Default")
      (node (ref "CN1") (pin "19") (pinfunction "19_19") (pintype "bidirectional"))
    )
    (net (code "137") (name "unconnected-(CN1-Pad20)") (class "Default")
      (node (ref "CN1") (pin "20") (pinfunction "20_20") (pintype "bidirectional"))
    )
    (net (code "138") (name "unconnected-(CN1-Pad21)") (class "Default")
      (node (ref "CN1") (pin "21") (pinfunction "21_21") (pintype "bidirectional"))
    )
    (net (code "139") (name "unconnected-(CN1-Pad22)") (class "Default")
      (node (ref "CN1") (pin "22") (pinfunction "22_22") (pintype "bidirectional"))
    )
    (net (code "140") (name "unconnected-(CN1-Pad25)") (class "Default")
      (node (ref "CN1") (pin "25") (pinfunction "25_25") (pintype "bidirectional"))
    )
    (net (code "141") (name "unconnected-(CN1-Pad26)") (class "Default")
      (node (ref "CN1") (pin "26") (pinfunction "26_26") (pintype "bidirectional"))
    )
    (net (code "142") (name "unconnected-(CN1-Pad27)") (class "Default")
      (node (ref "CN1") (pin "27") (pinfunction "27_27") (pintype "bidirectional"))
    )
    (net (code "143") (name "unconnected-(CN1-Pad28)") (class "Default")
      (node (ref "CN1") (pin "28") (pinfunction "28_28") (pintype "bidirectional"))
    )
    (net (code "144") (name "unconnected-(CN1-Pad29)") (class "Default")
      (node (ref "CN1") (pin "29") (pinfunction "29_29") (pintype "bidirectional"))
    )
    (net (code "145") (name "unconnected-(CN1-Pad30)") (class "Default")
      (node (ref "CN1") (pin "30") (pinfunction "30_30") (pintype "bidirectional"))
    )
    (net (code "146") (name "unconnected-(CN1-Pad31)") (class "Default")
      (node (ref "CN1") (pin "31") (pinfunction "31_31") (pintype "bidirectional"))
    )
    (net (code "147") (name "unconnected-(CN1-Pad32)") (class "Default")
      (node (ref "CN1") (pin "32") (pinfunction "32_32") (pintype "bidirectional"))
    )
    (net (code "148") (name "unconnected-(CN1-Pad33)") (class "Default")
      (node (ref "CN1") (pin "33") (pinfunction "33_33") (pintype "bidirectional"))
    )
    (net (code "149") (name "unconnected-(CN1-Pad34)") (class "Default")
      (node (ref "CN1") (pin "34") (pinfunction "34_34") (pintype "bidirectional"))
    )
    (net (code "150") (name "unconnected-(CN1-Pad35)") (class "Default")
      (node (ref "CN1") (pin "35") (pinfunction "35_35") (pintype "bidirectional"))
    )
    (net (code "151") (name "unconnected-(CN1-Pad36)") (class "Default")
      (node (ref "CN1") (pin "36") (pinfunction "36_36") (pintype "bidirectional"))
    )
    (net (code "152") (name "unconnected-(CN1-Pad39)") (class "Default")
      (node (ref "CN1") (pin "39") (pinfunction "39_39") (pintype "bidirectional"))
    )
    (net (code "153") (name "unconnected-(CN1-Pad44)") (class "Default")
      (node (ref "CN1") (pin "44") (pinfunction "44_44") (pintype "bidirectional"))
    )
    (net (code "154") (name "unconnected-(CN1-Pad45)") (class "Default")
      (node (ref "CN1") (pin "45") (pinfunction "45_45") (pintype "bidirectional"))
    )
    (net (code "155") (name "unconnected-(CN1-Pad46)") (class "Default")
      (node (ref "CN1") (pin "46") (pinfunction "46_46") (pintype "bidirectional"))
    )
    (net (code "156") (name "unconnected-(CN1-Pad47)") (class "Default")
      (node (ref "CN1") (pin "47") (pinfunction "47_47") (pintype "bidirectional"))
    )
    (net (code "157") (name "unconnected-(CN1-Pad48)") (class "Default")
      (node (ref "CN1") (pin "48") (pinfunction "48_48") (pintype "bidirectional"))
    )
    (net (code "158") (name "unconnected-(CN1-Pad49)") (class "Default")
      (node (ref "CN1") (pin "49") (pinfunction "49_49") (pintype "bidirectional"))
    )
    (net (code "159") (name "unconnected-(CN1-Pad50)") (class "Default")
      (node (ref "CN1") (pin "50") (pinfunction "50_50") (pintype "bidirectional"))
    )
    (net (code "160") (name "unconnected-(CN2-Pad1)") (class "Default")
      (node (ref "CN2") (pin "1") (pinfunction "1_1") (pintype "bidirectional"))
    )
    (net (code "161") (name "unconnected-(CN2-Pad2)") (class "Default")
      (node (ref "CN2") (pin "2") (pinfunction "2_2") (pintype "bidirectional"))
    )
    (net (code "162") (name "unconnected-(CN2-Pad3)") (class "Default")
      (node (ref "CN2") (pin "3") (pinfunction "3_3") (pintype "bidirectional"))
    )
    (net (code "163") (name "unconnected-(CN2-Pad4)") (class "Default")
      (node (ref "CN2") (pin "4") (pinfunction "4_4") (pintype "bidirectional"))
    )
    (net (code "164") (name "unconnected-(CN2-Pad5)") (class "Default")
      (node (ref "CN2") (pin "5") (pinfunction "5_5") (pintype "bidirectional"))
    )
    (net (code "165") (name "unconnected-(CN2-Pad6)") (class "Default")
      (node (ref "CN2") (pin "6") (pinfunction "6_6") (pintype "bidirectional"))
    )
    (net (code "166") (name "unconnected-(CN2-Pad7)") (class "Default")
      (node (ref "CN2") (pin "7") (pinfunction "7_7") (pintype "bidirectional"))
    )
    (net (code "167") (name "unconnected-(CN2-Pad8)") (class "Default")
      (node (ref "CN2") (pin "8") (pinfunction "8_8") (pintype "bidirectional"))
    )
    (net (code "168") (name "unconnected-(CN2-Pad9)") (class "Default")
      (node (ref "CN2") (pin "9") (pinfunction "9_9") (pintype "bidirectional"))
    )
    (net (code "169") (name "unconnected-(CN2-Pad10)") (class "Default")
      (node (ref "CN2") (pin "10") (pinfunction "10_10") (pintype "bidirectional"))
    )
    (net (code "170") (name "unconnected-(CN2-Pad11)") (class "Default")
      (node (ref "CN2") (pin "11") (pinfunction "11_11") (pintype "bidirectional"))
    )
    (net (code "171") (name "unconnected-(CN2-Pad12)") (class "Default")
      (node (ref "CN2") (pin "12") (pinfunction "12_12") (pintype "bidirectional"))
    )
    (net (code "172") (name "unconnected-(CN2-Pad15)") (class "Default")
      (node (ref "CN2") (pin "15") (pinfunction "15_15") (pintype "bidirectional"))
    )
    (net (code "173") (name "unconnected-(CN2-Pad16)") (class "Default")
      (node (ref "CN2") (pin "16") (pinfunction "16_16") (pintype "bidirectional"))
    )
    (net (code "174") (name "unconnected-(CN2-Pad17)") (class "Default")
      (node (ref "CN2") (pin "17") (pinfunction "17_17") (pintype "bidirectional"))
    )
    (net (code "175") (name "unconnected-(CN2-Pad18)") (class "Default")
      (node (ref "CN2") (pin "18") (pinfunction "18_18") (pintype "bidirectional"))
    )
    (net (code "176") (name "unconnected-(CN2-Pad19)") (class "Default")
      (node (ref "CN2") (pin "19") (pinfunction "19_19") (pintype "bidirectional"))
    )
    (net (code "177") (name "unconnected-(CN2-Pad20)") (class "Default")
      (node (ref "CN2") (pin "20") (pinfunction "20_20") (pintype "bidirectional"))
    )
    (net (code "178") (name "unconnected-(CN2-Pad21)") (class "Default")
      (node (ref "CN2") (pin "21") (pinfunction "21_21") (pintype "bidirectional"))
    )
    (net (code "179") (name "unconnected-(CN2-Pad22)") (class "Default")
      (node (ref "CN2") (pin "22") (pinfunction "22_22") (pintype "bidirectional"))
    )
    (net (code "180") (name "unconnected-(CN2-Pad23)") (class "Default")
      (node (ref "CN2") (pin "23") (pinfunction "23_23") (pintype "bidirectional"))
    )
    (net (code "181") (name "unconnected-(CN2-Pad24)") (class "Default")
      (node (ref "CN2") (pin "24") (pinfunction "24_24") (pintype "bidirectional"))
    )
    (net (code "182") (name "unconnected-(CN2-Pad30)") (class "Default")
      (node (ref "CN2") (pin "30") (pinfunction "30_30") (pintype "bidirectional"))
    )
    (net (code "183") (name "unconnected-(CN2-Pad31)") (class "Default")
      (node (ref "CN2") (pin "31") (pinfunction "31_31") (pintype "bidirectional"))
    )
    (net (code "184") (name "unconnected-(CN2-Pad32)") (class "Default")
      (node (ref "CN2") (pin "32") (pinfunction "32_32") (pintype "bidirectional"))
    )
    (net (code "185") (name "unconnected-(CN2-Pad33)") (class "Default")
      (node (ref "CN2") (pin "33") (pinfunction "33_33") (pintype "bidirectional"))
    )
    (net (code "186") (name "unconnected-(CN2-Pad34)") (class "Default")
      (node (ref "CN2") (pin "34") (pinfunction "34_34") (pintype "bidirectional"))
    )
    (net (code "187") (name "unconnected-(CN2-Pad35)") (class "Default")
      (node (ref "CN2") (pin "35") (pinfunction "35_35") (pintype "bidirectional"))
    )
    (net (code "188") (name "unconnected-(CN2-Pad36)") (class "Default")
      (node (ref "CN2") (pin "36") (pinfunction "36_36") (pintype "bidirectional"))
    )
    (net (code "189") (name "unconnected-(CN2-Pad37)") (class "Default")
      (node (ref "CN2") (pin "37") (pinfunction "37_37") (pintype "bidirectional"))
    )
    (net (code "190") (name "unconnected-(CN2-Pad38)") (class "Default")
      (node (ref "CN2") (pin "38") (pinfunction "38_38") (pintype "bidirectional"))
    )
    (net (code "191") (name "unconnected-(CN2-Pad39)") (class "Default")
      (node (ref "CN2") (pin "39") (pinfunction "39_39") (pintype "bidirectional"))
    )
    (net (code "192") (name "unconnected-(CN2-Pad40)") (class "Default")
      (node (ref "CN2") (pin "40") (pinfunction "40_40") (pintype "bidirectional"))
    )
    (net (code "193") (name "unconnected-(CN2-Pad41)") (class "Default")
      (node (ref "CN2") (pin "41") (pinfunction "41_41") (pintype "bidirectional"))
    )
    (net (code "194") (name "unconnected-(CN2-Pad42)") (class "Default")
      (node (ref "CN2") (pin "42") (pinfunction "42_42") (pintype "bidirectional"))
    )
    (net (code "195") (name "unconnected-(CN2-Pad43)") (class "Default")
      (node (ref "CN2") (pin "43") (pinfunction "43_43") (pintype "bidirectional"))
    )
    (net (code "196") (name "unconnected-(CN2-Pad44)") (class "Default")
      (node (ref "CN2") (pin "44") (pinfunction "44_44") (pintype "bidirectional"))
    )
    (net (code "197") (name "unconnected-(CN2-Pad45)") (class "Default")
      (node (ref "CN2") (pin "45") (pinfunction "45_45") (pintype "bidirectional"))
    )
    (net (code "198") (name "unconnected-(CN2-Pad46)") (class "Default")
      (node (ref "CN2") (pin "46") (pinfunction "46_46") (pintype "bidirectional"))
    )
    (net (code "199") (name "unconnected-(CN2-Pad47)") (class "Default")
      (node (ref "CN2") (pin "47") (pinfunction "47_47") (pintype "bidirectional"))
    )
    (net (code "200") (name "unconnected-(CN2-Pad48)") (class "Default")
      (node (ref "CN2") (pin "48") (pinfunction "48_48") (pintype "bidirectional"))
    )
    (net (code "201") (name "unconnected-(CN2-Pad49)") (class "Default")
      (node (ref "CN2") (pin "49") (pinfunction "49_49") (pintype "bidirectional"))
    )
    (net (code "202") (name "unconnected-(CN2-Pad50)") (class "Default")
      (node (ref "CN2") (pin "50") (pinfunction "50_50") (pintype "bidirectional"))
    )
    (net (code "203") (name "unconnected-(IC1-DIO3-Pad11)") (class "Default")
      (node (ref "IC1") (pin "11") (pinfunction "DIO3_11") (pintype "bidirectional"))
    )
    (net (code "204") (name "unconnected-(IC1-DIO4-Pad12)") (class "Default")
      (node (ref "IC1") (pin "12") (pinfunction "DIO4_12") (pintype "bidirectional"))
    )
    (net (code "205") (name "unconnected-(IC1-DIO5-Pad13)") (class "Default")
      (node (ref "IC1") (pin "13") (pinfunction "DIO5_13") (pintype "bidirectional"))
    )
    (net (code "206") (name "unconnected-(IC1-PA_BOOST-Pad27)") (class "Default")
      (node (ref "IC1") (pin "27") (pinfunction "PA_BOOST_27") (pintype "bidirectional"))
    )
    (net (code "207") (name "unconnected-(IC1-RXTX{slash}RFMOD-Pad20)") (class "Default")
      (node (ref "IC1") (pin "20") (pinfunction "RXTX/RFMOD_20") (pintype "bidirectional"))
    )
    (net (code "208") (name "unconnected-(IC4-CMISO1{slash}PB4-Pad40)") (class "Default")
      (node (ref "IC4") (pin "40") (pinfunction "CMISO1/PB4_40") (pintype "bidirectional"))
    )
    (net (code "209") (name "unconnected-(IC4-PC14{slash}OSC32_IN-Pad3)") (class "Default")
      (node (ref "IC4") (pin "3") (pinfunction "PC14/OSC32_IN_3") (pintype "bidirectional"))
    )
    (net (code "210") (name "unconnected-(IC4-PC15{slash}OSC32_OUT-Pad4)") (class "Default")
      (node (ref "IC4") (pin "4") (pinfunction "PC15/OSC32_OUT_4") (pintype "bidirectional"))
    )
    (net (code "211") (name "unconnected-(OCP1-GATEP-Pad2)") (class "Default")
      (node (ref "OCP1") (pin "2") (pinfunction "GATEP_2") (pintype "bidirectional"))
    )
    (net (code "212") (name "unconnected-(OCP1-~{PWRGD}-Pad5)") (class "Default")
      (node (ref "OCP1") (pin "5") (pinfunction "~{PWRGD}_5") (pintype "bidirectional"))
    )
    (net (code "213") (name "unconnected-(RFSW1-N{slash}C-Pad8)") (class "Default")
      (node (ref "RFSW1") (pin "8") (pinfunction "N/C_8") (pintype "bidirectional"))
    )
    (net (code "214") (name "unconnected-(RFSW1-N{slash}C-Pad12)") (class "Default")
      (node (ref "RFSW1") (pin "12") (pinfunction "N/C_12") (pintype "bidirectional"))
    )
    (net (code "215") (name "unconnected-(RFSW1-N{slash}C-Pad14)") (class "Default")
      (node (ref "RFSW1") (pin "14") (pinfunction "N/C_14") (pintype "bidirectional"))
    )
    (net (code "216") (name "unconnected-(RFSW1-PD-Pad15)") (class "Default")
      (node (ref "RFSW1") (pin "15") (pinfunction "PD_15") (pintype "bidirectional"))
    )
    (net (code "217") (name "unconnected-(U3-N.C.-Pad3)") (class "Default")
      (node (ref "U3") (pin "3") (pinfunction "N.C._3") (pintype "bidirectional"))
    )
    (net (code "218") (name "unconnected-(U4-ANT-Pad6)") (class "Default")
      (node (ref "U4") (pin "6") (pinfunction "ANT_6") (pintype "bidirectional"))
    )
    (net (code "219") (name "unconnected-(U4-NC-Pad5)") (class "Default")
      (node (ref "U4") (pin "5") (pinfunction "NC_5") (pintype "bidirectional"))
    )
    (net (code "220") (name "unconnected-(U4-NC-Pad11)") (class "Default")
      (node (ref "U4") (pin "11") (pinfunction "NC_11") (pintype "bidirectional"))
    )
    (net (code "221") (name "unconnected-(U4-TX-Pad2)") (class "Default")
      (node (ref "U4") (pin "2") (pinfunction "TX_2") (pintype "bidirectional"))
    )
  )
)
